# 2017_CARTE_MOFSET.net
KiCad netlist of a schematic drawn in Altium Designer
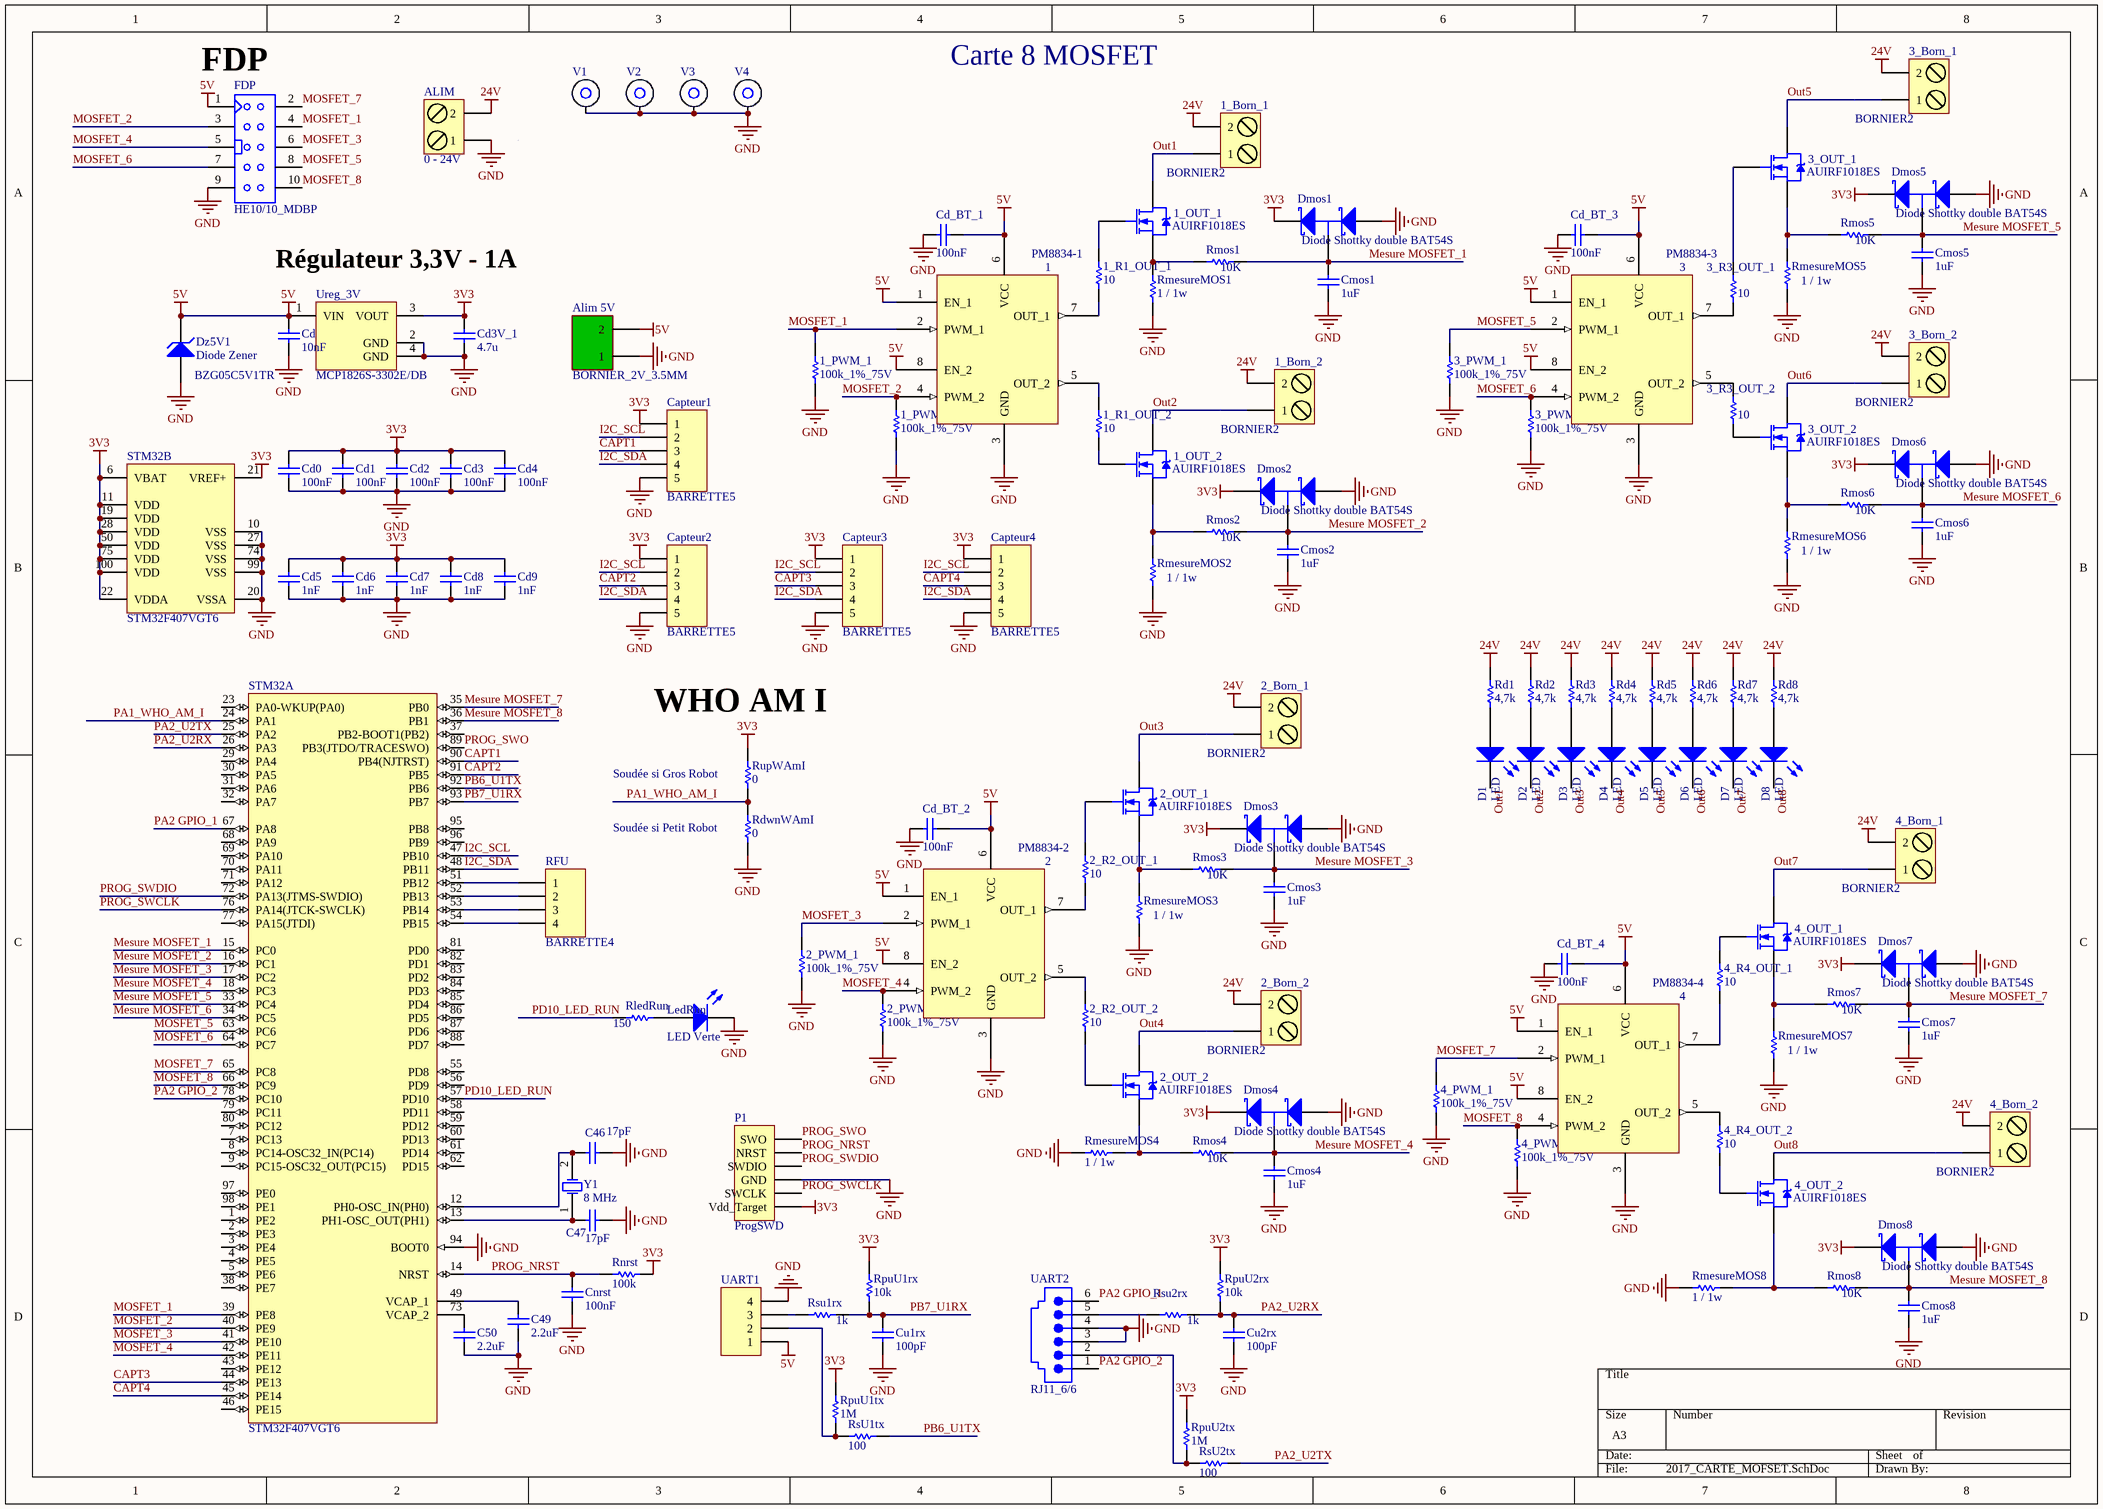
[diagram p0: 2017_CARTE_MOFSET.SchDoc]

(export (version "E")
  (design (tool "Eeschema 10.0.6"))
  (components
    (comp (ref "1")
      (value "PM8834-1")
      (footprint "SO8_N")
      (description "4 A dual low-side MOSFET driver")
      (libsource (lib "_ROBOT") (part "PM8834"))
    )
    (comp (ref "1_Born_1")
      (value "BORNIER2")
      (footprint "BORNIER2")
      (description "Terminal blocks, 2 pins, pitch=5mm")
      (libsource (lib "Connecteur") (part "BORNIER2"))
    )
    (comp (ref "1_Born_2")
      (value "BORNIER2")
      (footprint "BORNIER2")
      (description "Terminal blocks, 2 pins, pitch=5mm")
      (libsource (lib "Connecteur") (part "BORNIER2"))
    )
    (comp (ref "1_OUT_1")
      (value "AUIRF1018ES")
      (footprint "D2PAK_GROS_PAD")
      (description "HEXFET N-Channel Power MOSFET")
      (fields (field (name "PUBLISHER") "Altium Limited"))
      (libsource (lib "IR Discrete MOSFET - Power") (part "IRF1010S"))
    )
    (comp (ref "1_OUT_2")
      (value "AUIRF1018ES")
      (footprint "D2PAK_GROS_PAD")
      (description "HEXFET N-Channel Power MOSFET")
      (fields (field (name "PUBLISHER") "Altium Limited"))
      (libsource (lib "IR Discrete MOSFET - Power") (part "IRF1010S"))
    )
    (comp (ref "1_PWM_1")
      (value "100k_1%_75V")
      (footprint "R1206_N")
      (description "Resistor")
      (fields (field (name "PUBLISHER") "Altium Limited"))
      (libsource (lib "DG_Resistance") (part "Resistor"))
    )
    (comp (ref "1_PWM_2")
      (value "100k_1%_75V")
      (footprint "R1206_N")
      (description "Resistor")
      (fields (field (name "PUBLISHER") "Altium Limited"))
      (libsource (lib "DG_Resistance") (part "Resistor"))
    )
    (comp (ref "1_R1_OUT_1")
      (value "10")
      (footprint "R1206_N")
      (description "Resistor")
      (fields (field (name "PUBLISHER") "Altium Limited"))
      (libsource (lib "_ROBOT") (part "Resistor"))
    )
    (comp (ref "1_R1_OUT_2")
      (value "10")
      (footprint "R1206_N")
      (description "Resistor")
      (fields (field (name "PUBLISHER") "Altium Limited"))
      (libsource (lib "_ROBOT") (part "Resistor"))
    )
    (comp (ref "2")
      (value "PM8834-2")
      (footprint "SO8_N")
      (description "4 A dual low-side MOSFET driver")
      (libsource (lib "_ROBOT") (part "PM8834"))
    )
    (comp (ref "2_Born_1")
      (value "BORNIER2")
      (footprint "BORNIER2")
      (description "Terminal blocks, 2 pins, pitch=5mm")
      (libsource (lib "Connecteur") (part "BORNIER2"))
    )
    (comp (ref "2_Born_2")
      (value "BORNIER2")
      (footprint "BORNIER2")
      (description "Terminal blocks, 2 pins, pitch=5mm")
      (libsource (lib "Connecteur") (part "BORNIER2"))
    )
    (comp (ref "2_OUT_1")
      (value "AUIRF1018ES")
      (footprint "D2PAK_GROS_PAD")
      (description "HEXFET N-Channel Power MOSFET")
      (fields (field (name "PUBLISHER") "Altium Limited"))
      (libsource (lib "IR Discrete MOSFET - Power") (part "IRF1010S"))
    )
    (comp (ref "2_OUT_2")
      (value "AUIRF1018ES")
      (footprint "D2PAK_GROS_PAD")
      (description "HEXFET N-Channel Power MOSFET")
      (fields (field (name "PUBLISHER") "Altium Limited"))
      (libsource (lib "IR Discrete MOSFET - Power") (part "IRF1010S"))
    )
    (comp (ref "2_PWM_1")
      (value "100k_1%_75V")
      (footprint "R1206_N")
      (description "Resistor")
      (fields (field (name "PUBLISHER") "Altium Limited"))
      (libsource (lib "DG_Resistance") (part "Resistor"))
    )
    (comp (ref "2_PWM_2")
      (value "100k_1%_75V")
      (footprint "R1206_N")
      (description "Resistor")
      (fields (field (name "PUBLISHER") "Altium Limited"))
      (libsource (lib "DG_Resistance") (part "Resistor"))
    )
    (comp (ref "2_R2_OUT_1")
      (value "10")
      (footprint "R1206_N")
      (description "Resistor")
      (fields (field (name "PUBLISHER") "Altium Limited"))
      (libsource (lib "_ROBOT") (part "Resistor"))
    )
    (comp (ref "2_R2_OUT_2")
      (value "10")
      (footprint "R1206_N")
      (description "Resistor")
      (fields (field (name "PUBLISHER") "Altium Limited"))
      (libsource (lib "_ROBOT") (part "Resistor"))
    )
    (comp (ref "3")
      (value "PM8834-3")
      (footprint "SO8_N")
      (description "4 A dual low-side MOSFET driver")
      (libsource (lib "_ROBOT") (part "PM8834"))
    )
    (comp (ref "3_Born_1")
      (value "BORNIER2")
      (footprint "BORNIER2")
      (description "Terminal blocks, 2 pins, pitch=5mm")
      (libsource (lib "Connecteur") (part "BORNIER2"))
    )
    (comp (ref "3_Born_2")
      (value "BORNIER2")
      (footprint "BORNIER2")
      (description "Terminal blocks, 2 pins, pitch=5mm")
      (libsource (lib "Connecteur") (part "BORNIER2"))
    )
    (comp (ref "3_OUT_1")
      (value "AUIRF1018ES")
      (footprint "D2PAK_GROS_PAD")
      (description "HEXFET N-Channel Power MOSFET")
      (fields (field (name "PUBLISHER") "Altium Limited"))
      (libsource (lib "IR Discrete MOSFET - Power") (part "IRF1010S"))
    )
    (comp (ref "3_OUT_2")
      (value "AUIRF1018ES")
      (footprint "D2PAK_GROS_PAD")
      (description "HEXFET N-Channel Power MOSFET")
      (fields (field (name "PUBLISHER") "Altium Limited"))
      (libsource (lib "IR Discrete MOSFET - Power") (part "IRF1010S"))
    )
    (comp (ref "3_PWM_1")
      (value "100k_1%_75V")
      (footprint "R1206_N")
      (description "Resistor")
      (fields (field (name "PUBLISHER") "Altium Limited"))
      (libsource (lib "DG_Resistance") (part "Resistor"))
    )
    (comp (ref "3_PWM_2")
      (value "100k_1%_75V")
      (footprint "R1206_N")
      (description "Resistor")
      (fields (field (name "PUBLISHER") "Altium Limited"))
      (libsource (lib "DG_Resistance") (part "Resistor"))
    )
    (comp (ref "3_R3_OUT_1")
      (value "10")
      (footprint "R1206_N")
      (description "Resistor")
      (fields (field (name "PUBLISHER") "Altium Limited"))
      (libsource (lib "_ROBOT") (part "Resistor"))
    )
    (comp (ref "3_R3_OUT_2")
      (value "10")
      (footprint "R1206_N")
      (description "Resistor")
      (fields (field (name "PUBLISHER") "Altium Limited"))
      (libsource (lib "_ROBOT") (part "Resistor"))
    )
    (comp (ref "4")
      (value "PM8834-4")
      (footprint "SO8_N")
      (description "4 A dual low-side MOSFET driver")
      (libsource (lib "_ROBOT") (part "PM8834"))
    )
    (comp (ref "4_Born_1")
      (value "BORNIER2")
      (footprint "BORNIER2")
      (description "Terminal blocks, 2 pins, pitch=5mm")
      (libsource (lib "Connecteur") (part "BORNIER2"))
    )
    (comp (ref "4_Born_2")
      (value "BORNIER2")
      (footprint "BORNIER2")
      (description "Terminal blocks, 2 pins, pitch=5mm")
      (libsource (lib "Connecteur") (part "BORNIER2"))
    )
    (comp (ref "4_OUT_1")
      (value "AUIRF1018ES")
      (footprint "D2PAK_GROS_PAD")
      (description "HEXFET N-Channel Power MOSFET")
      (fields (field (name "PUBLISHER") "Altium Limited"))
      (libsource (lib "IR Discrete MOSFET - Power") (part "IRF1010S"))
    )
    (comp (ref "4_OUT_2")
      (value "AUIRF1018ES")
      (footprint "D2PAK_GROS_PAD")
      (description "HEXFET N-Channel Power MOSFET")
      (fields (field (name "PUBLISHER") "Altium Limited"))
      (libsource (lib "IR Discrete MOSFET - Power") (part "IRF1010S"))
    )
    (comp (ref "4_PWM_1")
      (value "100k_1%_75V")
      (footprint "R1206_N")
      (description "Resistor")
      (fields (field (name "PUBLISHER") "Altium Limited"))
      (libsource (lib "DG_Resistance") (part "Resistor"))
    )
    (comp (ref "4_PWM_2")
      (value "100k_1%_75V")
      (footprint "R1206_N")
      (description "Resistor")
      (fields (field (name "PUBLISHER") "Altium Limited"))
      (libsource (lib "DG_Resistance") (part "Resistor"))
    )
    (comp (ref "4_R4_OUT_1")
      (value "10")
      (footprint "R1206_N")
      (description "Resistor")
      (fields (field (name "PUBLISHER") "Altium Limited"))
      (libsource (lib "_ROBOT") (part "Resistor"))
    )
    (comp (ref "4_R4_OUT_2")
      (value "10")
      (footprint "R1206_N")
      (description "Resistor")
      (fields (field (name "PUBLISHER") "Altium Limited"))
      (libsource (lib "_ROBOT") (part "Resistor"))
    )
    (comp (ref "ALIM")
      (value "0 - 24V")
      (footprint "BORNIER2_FEM_COUDE")
      (description "Terminal blocks, 2 pins, pitch=5mm")
      (libsource (lib "miniprojet") (part "BORNIER2"))
    )
    (comp (ref "Alim 5V")
      (value "BORNIER_2V_3.5MM")
      (footprint "BORNIER_2V_3.5MM")
      (libsource (lib "Connecteur") (part "BORNIER_2V_3.5MM"))
    )
    (comp (ref "C46")
      (value "17pF")
      (footprint "C0805_N")
      (description "Capacitor")
      (fields (field (name "PUBLISHER") "Altium Limited"))
      (libsource (lib "_ROBOT") (part "Condensateur"))
    )
    (comp (ref "C47")
      (value "17pF")
      (footprint "C0805_N")
      (description "Capacitor")
      (fields (field (name "PUBLISHER") "Altium Limited"))
      (libsource (lib "_ROBOT") (part "Condensateur"))
    )
    (comp (ref "C49")
      (value "2.2uF")
      (footprint "C0805_N")
      (description "Capacitor")
      (fields (field (name "PUBLISHER") "Altium Limited"))
      (libsource (lib "_ROBOT") (part "Condensateur"))
    )
    (comp (ref "C50")
      (value "2.2uF")
      (footprint "C0805_N")
      (description "Capacitor")
      (fields (field (name "PUBLISHER") "Altium Limited"))
      (libsource (lib "_ROBOT") (part "Condensateur"))
    )
    (comp (ref "Capteur1")
      (value "BARRETTE5")
      (footprint "MOLEX5_2.50MM")
      (description "Header, 5-Pin")
      (fields (field (name "PUBLISHER") "Altium Limited"))
      (libsource (lib "Connecteur") (part "BARRETTE5"))
    )
    (comp (ref "Capteur2")
      (value "BARRETTE5")
      (footprint "MOLEX5_2.50MM")
      (description "Header, 5-Pin")
      (fields (field (name "PUBLISHER") "Altium Limited"))
      (libsource (lib "Connecteur") (part "BARRETTE5"))
    )
    (comp (ref "Capteur3")
      (value "BARRETTE5")
      (footprint "MOLEX5_2.50MM")
      (description "Header, 5-Pin")
      (fields (field (name "PUBLISHER") "Altium Limited"))
      (libsource (lib "Connecteur") (part "BARRETTE5"))
    )
    (comp (ref "Capteur4")
      (value "BARRETTE5")
      (footprint "MOLEX5_2.50MM")
      (description "Header, 5-Pin")
      (fields (field (name "PUBLISHER") "Altium Limited"))
      (libsource (lib "Connecteur") (part "BARRETTE5"))
    )
    (comp (ref "Cd")
      (value "10nF")
      (footprint "C1206_N")
      (description "Capacitor")
      (fields (field (name "PUBLISHER") "Altium Limited"))
      (libsource (lib "_ROBOT") (part "Condensateur"))
    )
    (comp (ref "Cd0")
      (value "100nF")
      (footprint "C0805_N")
      (description "Capacitor")
      (fields (field (name "PUBLISHER") "Altium Limited"))
      (libsource (lib "_ROBOT") (part "Condensateur"))
    )
    (comp (ref "Cd1")
      (value "100nF")
      (footprint "C0805_N")
      (description "Capacitor")
      (fields (field (name "PUBLISHER") "Altium Limited"))
      (libsource (lib "_ROBOT") (part "Condensateur"))
    )
    (comp (ref "Cd2")
      (value "100nF")
      (footprint "C0805_N")
      (description "Capacitor")
      (fields (field (name "PUBLISHER") "Altium Limited"))
      (libsource (lib "_ROBOT") (part "Condensateur"))
    )
    (comp (ref "Cd3")
      (value "100nF")
      (footprint "C0805_N")
      (description "Capacitor")
      (fields (field (name "PUBLISHER") "Altium Limited"))
      (libsource (lib "_ROBOT") (part "Condensateur"))
    )
    (comp (ref "Cd3V_1")
      (value "4.7u")
      (footprint "C0805_N")
      (description "Capacitor")
      (fields (field (name "PUBLISHER") "Altium Limited"))
      (libsource (lib "DG_Condensateur") (part "Capacitor"))
    )
    (comp (ref "Cd4")
      (value "100nF")
      (footprint "C0805_N")
      (description "Capacitor")
      (fields (field (name "PUBLISHER") "Altium Limited"))
      (libsource (lib "_ROBOT") (part "Condensateur"))
    )
    (comp (ref "Cd5")
      (value "1nF")
      (footprint "C0805_N")
      (description "Capacitor")
      (fields (field (name "PUBLISHER") "Altium Limited"))
      (libsource (lib "_ROBOT") (part "Condensateur"))
    )
    (comp (ref "Cd6")
      (value "1nF")
      (footprint "C0805_N")
      (description "Capacitor")
      (fields (field (name "PUBLISHER") "Altium Limited"))
      (libsource (lib "_ROBOT") (part "Condensateur"))
    )
    (comp (ref "Cd7")
      (value "1nF")
      (footprint "C0805_N")
      (description "Capacitor")
      (fields (field (name "PUBLISHER") "Altium Limited"))
      (libsource (lib "_ROBOT") (part "Condensateur"))
    )
    (comp (ref "Cd8")
      (value "1nF")
      (footprint "C0805_N")
      (description "Capacitor")
      (fields (field (name "PUBLISHER") "Altium Limited"))
      (libsource (lib "_ROBOT") (part "Condensateur"))
    )
    (comp (ref "Cd9")
      (value "1nF")
      (footprint "C0805_N")
      (description "Capacitor")
      (fields (field (name "PUBLISHER") "Altium Limited"))
      (libsource (lib "_ROBOT") (part "Condensateur"))
    )
    (comp (ref "Cd_BT_1")
      (value "100nF")
      (footprint "C0805_N")
      (description "Capacitor")
      (fields (field (name "PUBLISHER") "Altium Limited"))
      (libsource (lib "_ROBOT") (part "Condensateur"))
    )
    (comp (ref "Cd_BT_2")
      (value "100nF")
      (footprint "C0805_N")
      (description "Capacitor")
      (fields (field (name "PUBLISHER") "Altium Limited"))
      (libsource (lib "_ROBOT") (part "Condensateur"))
    )
    (comp (ref "Cd_BT_3")
      (value "100nF")
      (footprint "C0805_N")
      (description "Capacitor")
      (fields (field (name "PUBLISHER") "Altium Limited"))
      (libsource (lib "_ROBOT") (part "Condensateur"))
    )
    (comp (ref "Cd_BT_4")
      (value "100nF")
      (footprint "C0805_N")
      (description "Capacitor")
      (fields (field (name "PUBLISHER") "Altium Limited"))
      (libsource (lib "_ROBOT") (part "Condensateur"))
    )
    (comp (ref "Cmos1")
      (value "1uF")
      (footprint "C0805_N")
      (description "Capacitor")
      (fields (field (name "PUBLISHER") "Altium Limited"))
      (libsource (lib "_ROBOT") (part "Condensateur"))
    )
    (comp (ref "Cmos2")
      (value "1uF")
      (footprint "C0805_N")
      (description "Capacitor")
      (fields (field (name "PUBLISHER") "Altium Limited"))
      (libsource (lib "_ROBOT") (part "Condensateur"))
    )
    (comp (ref "Cmos3")
      (value "1uF")
      (footprint "C0805_N")
      (description "Capacitor")
      (fields (field (name "PUBLISHER") "Altium Limited"))
      (libsource (lib "_ROBOT") (part "Condensateur"))
    )
    (comp (ref "Cmos4")
      (value "1uF")
      (footprint "C0805_N")
      (description "Capacitor")
      (fields (field (name "PUBLISHER") "Altium Limited"))
      (libsource (lib "_ROBOT") (part "Condensateur"))
    )
    (comp (ref "Cmos5")
      (value "1uF")
      (footprint "C0805_N")
      (description "Capacitor")
      (fields (field (name "PUBLISHER") "Altium Limited"))
      (libsource (lib "_ROBOT") (part "Condensateur"))
    )
    (comp (ref "Cmos6")
      (value "1uF")
      (footprint "C0805_N")
      (description "Capacitor")
      (fields (field (name "PUBLISHER") "Altium Limited"))
      (libsource (lib "_ROBOT") (part "Condensateur"))
    )
    (comp (ref "Cmos7")
      (value "1uF")
      (footprint "C0805_N")
      (description "Capacitor")
      (fields (field (name "PUBLISHER") "Altium Limited"))
      (libsource (lib "_ROBOT") (part "Condensateur"))
    )
    (comp (ref "Cmos8")
      (value "1uF")
      (footprint "C0805_N")
      (description "Capacitor")
      (fields (field (name "PUBLISHER") "Altium Limited"))
      (libsource (lib "_ROBOT") (part "Condensateur"))
    )
    (comp (ref "Cnrst")
      (value "100nF")
      (footprint "C0805_N")
      (description "Capacitor")
      (fields (field (name "PUBLISHER") "Altium Limited"))
      (libsource (lib "_ROBOT") (part "Condensateur"))
    )
    (comp (ref "Cu1rx")
      (value "100pF")
      (footprint "C0805_N")
      (description "Capacitor")
      (fields (field (name "PUBLISHER") "Altium Limited"))
      (libsource (lib "_ROBOT") (part "Condensateur"))
    )
    (comp (ref "Cu2rx")
      (value "100pF")
      (footprint "C0805_N")
      (description "Capacitor")
      (fields (field (name "PUBLISHER") "Altium Limited"))
      (libsource (lib "_ROBOT") (part "Condensateur"))
    )
    (comp (ref "D1")
      (value "LED")
      (footprint "LED_0805")
      (description "Typical LED")
      (fields (field (name "PUBLISHER") "Altium Limited"))
      (libsource (lib "_ROBOT") (part "LED"))
    )
    (comp (ref "D2")
      (value "LED")
      (footprint "LED_0805")
      (description "Typical LED")
      (fields (field (name "PUBLISHER") "Altium Limited"))
      (libsource (lib "_ROBOT") (part "LED"))
    )
    (comp (ref "D3")
      (value "LED")
      (footprint "LED_0805")
      (description "Typical LED")
      (fields (field (name "PUBLISHER") "Altium Limited"))
      (libsource (lib "_ROBOT") (part "LED"))
    )
    (comp (ref "D4")
      (value "LED")
      (footprint "LED_0805")
      (description "Typical LED")
      (fields (field (name "PUBLISHER") "Altium Limited"))
      (libsource (lib "_ROBOT") (part "LED"))
    )
    (comp (ref "D5")
      (value "LED")
      (footprint "LED_0805")
      (description "Typical LED")
      (fields (field (name "PUBLISHER") "Altium Limited"))
      (libsource (lib "_ROBOT") (part "LED"))
    )
    (comp (ref "D6")
      (value "LED")
      (footprint "LED_0805")
      (description "Typical LED")
      (fields (field (name "PUBLISHER") "Altium Limited"))
      (libsource (lib "_ROBOT") (part "LED"))
    )
    (comp (ref "D7")
      (value "LED")
      (footprint "LED_0805")
      (description "Typical LED")
      (fields (field (name "PUBLISHER") "Altium Limited"))
      (libsource (lib "_ROBOT") (part "LED"))
    )
    (comp (ref "D8")
      (value "LED")
      (footprint "LED_0805")
      (description "Typical LED")
      (fields (field (name "PUBLISHER") "Altium Limited"))
      (libsource (lib "_ROBOT") (part "LED"))
    )
    (comp (ref "Dmos1")
      (value "Diode Shottky double BAT54S")
      (footprint "SOT23-3N")
      (description "DIODE SCHOTTKY DOUBLE")
      (fields (field (name "MANUFACTURER PART NUMBER") "BAT54S") (field (name "MANUFACTURER") "ZETEX"))
      (libsource (lib "_ROBOT") (part "Diode Shottky double BAT54S"))
    )
    (comp (ref "Dmos2")
      (value "Diode Shottky double BAT54S")
      (footprint "SOT23-3N")
      (description "DIODE SCHOTTKY DOUBLE")
      (fields (field (name "MANUFACTURER PART NUMBER") "BAT54S") (field (name "MANUFACTURER") "ZETEX"))
      (libsource (lib "_ROBOT") (part "Diode Shottky double BAT54S"))
    )
    (comp (ref "Dmos3")
      (value "Diode Shottky double BAT54S")
      (footprint "SOT23-3N")
      (description "DIODE SCHOTTKY DOUBLE")
      (fields (field (name "MANUFACTURER PART NUMBER") "BAT54S") (field (name "MANUFACTURER") "ZETEX"))
      (libsource (lib "_ROBOT") (part "Diode Shottky double BAT54S"))
    )
    (comp (ref "Dmos4")
      (value "Diode Shottky double BAT54S")
      (footprint "SOT23-3N")
      (description "DIODE SCHOTTKY DOUBLE")
      (fields (field (name "MANUFACTURER PART NUMBER") "BAT54S") (field (name "MANUFACTURER") "ZETEX"))
      (libsource (lib "_ROBOT") (part "Diode Shottky double BAT54S"))
    )
    (comp (ref "Dmos5")
      (value "Diode Shottky double BAT54S")
      (footprint "SOT23-3N")
      (description "DIODE SCHOTTKY DOUBLE")
      (fields (field (name "MANUFACTURER PART NUMBER") "BAT54S") (field (name "MANUFACTURER") "ZETEX"))
      (libsource (lib "_ROBOT") (part "Diode Shottky double BAT54S"))
    )
    (comp (ref "Dmos6")
      (value "Diode Shottky double BAT54S")
      (footprint "SOT23-3N")
      (description "DIODE SCHOTTKY DOUBLE")
      (fields (field (name "MANUFACTURER PART NUMBER") "BAT54S") (field (name "MANUFACTURER") "ZETEX"))
      (libsource (lib "_ROBOT") (part "Diode Shottky double BAT54S"))
    )
    (comp (ref "Dmos7")
      (value "Diode Shottky double BAT54S")
      (footprint "SOT23-3N")
      (description "DIODE SCHOTTKY DOUBLE")
      (fields (field (name "MANUFACTURER PART NUMBER") "BAT54S") (field (name "MANUFACTURER") "ZETEX"))
      (libsource (lib "_ROBOT") (part "Diode Shottky double BAT54S"))
    )
    (comp (ref "Dmos8")
      (value "Diode Shottky double BAT54S")
      (footprint "SOT23-3N")
      (description "DIODE SCHOTTKY DOUBLE")
      (fields (field (name "MANUFACTURER PART NUMBER") "BAT54S") (field (name "MANUFACTURER") "ZETEX"))
      (libsource (lib "_ROBOT") (part "Diode Shottky double BAT54S"))
    )
    (comp (ref "Dz5V1")
      (value "Diode Zener")
      (footprint "SMA Diode")
      (description "Zener Diode")
      (fields (field (name "ALTIUM_UNNAMED_1") "BZG05C5V1TR"))
      (libsource (lib "_ROBOT") (part "Diode Zener"))
    )
    (comp (ref "FDP")
      (value "HE10/10_MALE_DROIT_BAS_PROFIL")
      (footprint "HE10/10_M_D_BP")
      (description "EMBASE HE10/10 MALE DROIT BAS PROFIL")
      (fields (field (name "TYPE") "HE10/10_MDBP"))
      (libsource (lib "connecteurs") (part "HE10/10_MALE_DROIT_BAS_PROFIL"))
    )
    (comp (ref "LedRun")
      (value "LED Verte")
      (footprint "LED_0805")
      (description "Typical LED")
      (fields (field (name "PUBLISHER") "Altium Limited"))
      (libsource (lib "DG_LED") (part "LED"))
    )
    (comp (ref "P1")
      (value "ProgSWD")
      (footprint "HDR1X6")
      (description "Header, 6-Pin")
      (fields (field (name "PUBLISHER") "Altium Limited"))
      (libsource (lib "DG_Connecteur") (part "Header 6"))
    )
    (comp (ref "Rd1")
      (value "4,7k")
      (footprint "R1206_N")
      (description "Resistor")
      (fields (field (name "PUBLISHER") "Altium Limited"))
      (libsource (lib "_ROBOT") (part "Resistor"))
    )
    (comp (ref "Rd2")
      (value "4,7k")
      (footprint "R1206_N")
      (description "Resistor")
      (fields (field (name "PUBLISHER") "Altium Limited"))
      (libsource (lib "_ROBOT") (part "Resistor"))
    )
    (comp (ref "Rd3")
      (value "4,7k")
      (footprint "R1206_N")
      (description "Resistor")
      (fields (field (name "PUBLISHER") "Altium Limited"))
      (libsource (lib "_ROBOT") (part "Resistor"))
    )
    (comp (ref "Rd4")
      (value "4,7k")
      (footprint "R1206_N")
      (description "Resistor")
      (fields (field (name "PUBLISHER") "Altium Limited"))
      (libsource (lib "_ROBOT") (part "Resistor"))
    )
    (comp (ref "Rd5")
      (value "4,7k")
      (footprint "R1206_N")
      (description "Resistor")
      (fields (field (name "PUBLISHER") "Altium Limited"))
      (libsource (lib "_ROBOT") (part "Resistor"))
    )
    (comp (ref "Rd6")
      (value "4,7k")
      (footprint "R1206_N")
      (description "Resistor")
      (fields (field (name "PUBLISHER") "Altium Limited"))
      (libsource (lib "_ROBOT") (part "Resistor"))
    )
    (comp (ref "Rd7")
      (value "4,7k")
      (footprint "R1206_N")
      (description "Resistor")
      (fields (field (name "PUBLISHER") "Altium Limited"))
      (libsource (lib "_ROBOT") (part "Resistor"))
    )
    (comp (ref "Rd8")
      (value "4,7k")
      (footprint "R1206_N")
      (description "Resistor")
      (fields (field (name "PUBLISHER") "Altium Limited"))
      (libsource (lib "_ROBOT") (part "Resistor"))
    )
    (comp (ref "RdwnWAmI")
      (value "0")
      (footprint "R1206_N")
      (description "Resistor")
      (fields (field (name "PUBLISHER") "Altium Limited"))
      (libsource (lib "_ROBOT") (part "Resistor"))
    )
    (comp (ref "RFU")
      (value "BARRETTE4")
      (footprint "HE14_4")
      (description "Header, 4-Pin")
      (fields (field (name "PUBLISHER") "Altium Limited"))
      (libsource (lib "Connecteur") (part "BARRETTE4"))
    )
    (comp (ref "RledRun")
      (value "150")
      (footprint "R1206_N")
      (description "Resistor")
      (fields (field (name "PUBLISHER") "Altium Limited"))
      (libsource (lib "_ROBOT") (part "Resistor"))
    )
    (comp (ref "RmesureMOS1")
      (value "1 / 1w")
      (footprint "INDUCTANCE_CMS_1812")
      (description "Resistor")
      (fields (field (name "PUBLISHER") "Altium Limited"))
      (libsource (lib "_ROBOT") (part "Resistor"))
    )
    (comp (ref "RmesureMOS2")
      (value "1 / 1w")
      (footprint "INDUCTANCE_CMS_1812")
      (description "Resistor")
      (fields (field (name "PUBLISHER") "Altium Limited"))
      (libsource (lib "_ROBOT") (part "Resistor"))
    )
    (comp (ref "RmesureMOS3")
      (value "1 / 1w")
      (footprint "INDUCTANCE_CMS_1812")
      (description "Resistor")
      (fields (field (name "PUBLISHER") "Altium Limited"))
      (libsource (lib "_ROBOT") (part "Resistor"))
    )
    (comp (ref "RmesureMOS4")
      (value "1 / 1w")
      (footprint "INDUCTANCE_CMS_1812")
      (description "Resistor")
      (fields (field (name "PUBLISHER") "Altium Limited"))
      (libsource (lib "_ROBOT") (part "Resistor"))
    )
    (comp (ref "RmesureMOS5")
      (value "1 / 1w")
      (footprint "INDUCTANCE_CMS_1812")
      (description "Resistor")
      (fields (field (name "PUBLISHER") "Altium Limited"))
      (libsource (lib "_ROBOT") (part "Resistor"))
    )
    (comp (ref "RmesureMOS6")
      (value "1 / 1w")
      (footprint "INDUCTANCE_CMS_1812")
      (description "Resistor")
      (fields (field (name "PUBLISHER") "Altium Limited"))
      (libsource (lib "_ROBOT") (part "Resistor"))
    )
    (comp (ref "RmesureMOS7")
      (value "1 / 1w")
      (footprint "INDUCTANCE_CMS_1812")
      (description "Resistor")
      (fields (field (name "PUBLISHER") "Altium Limited"))
      (libsource (lib "_ROBOT") (part "Resistor"))
    )
    (comp (ref "RmesureMOS8")
      (value "1 / 1w")
      (footprint "INDUCTANCE_CMS_1812")
      (description "Resistor")
      (fields (field (name "PUBLISHER") "Altium Limited"))
      (libsource (lib "_ROBOT") (part "Resistor"))
    )
    (comp (ref "Rmos1")
      (value "10K")
      (footprint "R1206_N")
      (description "Resistor")
      (fields (field (name "PUBLISHER") "Altium Limited"))
      (libsource (lib "_ROBOT") (part "Resistor"))
    )
    (comp (ref "Rmos2")
      (value "10K")
      (footprint "R1206_N")
      (description "Resistor")
      (fields (field (name "PUBLISHER") "Altium Limited"))
      (libsource (lib "_ROBOT") (part "Resistor"))
    )
    (comp (ref "Rmos3")
      (value "10K")
      (footprint "R1206_N")
      (description "Resistor")
      (fields (field (name "PUBLISHER") "Altium Limited"))
      (libsource (lib "_ROBOT") (part "Resistor"))
    )
    (comp (ref "Rmos4")
      (value "10K")
      (footprint "R1206_N")
      (description "Resistor")
      (fields (field (name "PUBLISHER") "Altium Limited"))
      (libsource (lib "_ROBOT") (part "Resistor"))
    )
    (comp (ref "Rmos5")
      (value "10K")
      (footprint "R1206_N")
      (description "Resistor")
      (fields (field (name "PUBLISHER") "Altium Limited"))
      (libsource (lib "_ROBOT") (part "Resistor"))
    )
    (comp (ref "Rmos6")
      (value "10K")
      (footprint "R1206_N")
      (description "Resistor")
      (fields (field (name "PUBLISHER") "Altium Limited"))
      (libsource (lib "_ROBOT") (part "Resistor"))
    )
    (comp (ref "Rmos7")
      (value "10K")
      (footprint "R1206_N")
      (description "Resistor")
      (fields (field (name "PUBLISHER") "Altium Limited"))
      (libsource (lib "_ROBOT") (part "Resistor"))
    )
    (comp (ref "Rmos8")
      (value "10K")
      (footprint "R1206_N")
      (description "Resistor")
      (fields (field (name "PUBLISHER") "Altium Limited"))
      (libsource (lib "_ROBOT") (part "Resistor"))
    )
    (comp (ref "Rnrst")
      (value "100k")
      (footprint "R1206_N")
      (description "Resistor")
      (fields (field (name "PUBLISHER") "Altium Limited"))
      (libsource (lib "_ROBOT") (part "Resistor"))
    )
    (comp (ref "RpuU1rx")
      (value "10k")
      (footprint "R1206_N")
      (description "Resistor")
      (fields (field (name "PUBLISHER") "Altium Limited"))
      (libsource (lib "_ROBOT") (part "Resistor"))
    )
    (comp (ref "RpuU1tx")
      (value "1M")
      (footprint "R1206_N")
      (description "Resistor")
      (fields (field (name "PUBLISHER") "Altium Limited"))
      (libsource (lib "_ROBOT") (part "Resistor"))
    )
    (comp (ref "RpuU2rx")
      (value "10k")
      (footprint "R1206_N")
      (description "Resistor")
      (fields (field (name "PUBLISHER") "Altium Limited"))
      (libsource (lib "_ROBOT") (part "Resistor"))
    )
    (comp (ref "RpuU2tx")
      (value "1M")
      (footprint "R1206_N")
      (description "Resistor")
      (fields (field (name "PUBLISHER") "Altium Limited"))
      (libsource (lib "_ROBOT") (part "Resistor"))
    )
    (comp (ref "Rsu1rx")
      (value "1k")
      (footprint "R1206_N")
      (description "Resistor")
      (fields (field (name "PUBLISHER") "Altium Limited"))
      (libsource (lib "_ROBOT") (part "Resistor"))
    )
    (comp (ref "RsU1tx")
      (value "100")
      (footprint "R1206_N")
      (description "Resistor")
      (fields (field (name "PUBLISHER") "Altium Limited"))
      (libsource (lib "_ROBOT") (part "Resistor"))
    )
    (comp (ref "Rsu2rx")
      (value "1k")
      (footprint "R1206_N")
      (description "Resistor")
      (fields (field (name "PUBLISHER") "Altium Limited"))
      (libsource (lib "_ROBOT") (part "Resistor"))
    )
    (comp (ref "RsU2tx")
      (value "100")
      (footprint "R1206_N")
      (description "Resistor")
      (fields (field (name "PUBLISHER") "Altium Limited"))
      (libsource (lib "_ROBOT") (part "Resistor"))
    )
    (comp (ref "RupWAmI")
      (value "0")
      (footprint "R1206_N")
      (description "Resistor")
      (fields (field (name "PUBLISHER") "Altium Limited"))
      (libsource (lib "_ROBOT") (part "Resistor"))
    )
    (comp (ref "STM32")
      (value "STM32F407VGT6")
      (footprint "STM-LQFP100_N")
      (fields (field (name "MANUFACTURER") "STMicroelectronics"))
      (libsource (lib "STMicroelectronics STM32 F4") (part "STM32F407VGT6"))
    )
    (comp (ref "UART1")
      (value "BARRETTE4")
      (footprint "HDR1X4")
      (description "Header, 4-Pin")
      (fields (field (name "PUBLISHER") "Altium Limited"))
      (libsource (lib "Connecteur") (part "HDR1X4"))
    )
    (comp (ref "UART2")
      (value "RJ11_6/6")
      (footprint "RJ11_6/6")
      (description "Right Angle, Standard Profile, Offset Latch DECconnect, Flangeless PCB Jack")
      (fields (field (name "PUBLISHER") "Altium Limited"))
      (libsource (lib "Connecteur") (part "RJ11_6/6"))
    )
    (comp (ref "Ureg_3V")
      (value "MCP1826S-3302E/DB")
      (footprint "SOT223-4N")
      (description "1000 mA, Low Voltage, Low Quiescent Current LDO Regulator, 3-Pin SOT-223, Extended Temperature")
      (fields (field (name "PUBLISHER") "Altium Limited"))
      (libsource (lib "Microchip Power Mgt Line Regulator") (part "MCP1826S-3302E/DB"))
    )
    (comp (ref "V1")
      (value "Entretoise WURTH CMS")
      (footprint "ENTRETOISE_CMS")
      (description "Entretoise Wurth")
      (fields (field (name "PUBLISHER") "Damien Guitton"))
      (libsource (lib "_ROBOT") (part "Entretoise WURTH CMS"))
    )
    (comp (ref "V2")
      (value "Entretoise WURTH CMS")
      (footprint "ENTRETOISE_CMS")
      (description "Entretoise Wurth")
      (fields (field (name "PUBLISHER") "Damien Guitton"))
      (libsource (lib "_ROBOT") (part "Entretoise WURTH CMS"))
    )
    (comp (ref "V3")
      (value "Entretoise WURTH CMS")
      (footprint "ENTRETOISE_CMS")
      (description "Entretoise Wurth")
      (fields (field (name "PUBLISHER") "Damien Guitton"))
      (libsource (lib "_ROBOT") (part "Entretoise WURTH CMS"))
    )
    (comp (ref "V4")
      (value "Entretoise WURTH CMS")
      (footprint "ENTRETOISE_CMS")
      (description "Entretoise Wurth")
      (fields (field (name "PUBLISHER") "Damien Guitton"))
      (libsource (lib "_ROBOT") (part "Entretoise WURTH CMS"))
    )
    (comp (ref "Y1")
      (value "8 MHz")
      (footprint "HC49/4H_SMX")
      (description "Crystal Oscillator")
      (fields (field (name "PUBLISHER") "Altium Limited"))
      (libsource (lib "_ROBOT") (part "Quartz"))
    )
  )
  (nets
    (net (code "1") (name "/CAPT1") (class "Default")
      (node (ref "Capteur1") (pin "3") (pinfunction "3_3") (pintype "passive"))
      (node (ref "STM32") (pin "90") (pinfunction "PB4(NJTRST)_90") (pintype "bidirectional"))
    )
    (net (code "2") (name "/CAPT2") (class "Default")
      (node (ref "Capteur2") (pin "3") (pinfunction "3_3") (pintype "passive"))
      (node (ref "STM32") (pin "91") (pinfunction "PB5_91") (pintype "bidirectional"))
    )
    (net (code "3") (name "/CAPT3") (class "Default")
      (node (ref "Capteur3") (pin "3") (pinfunction "3_3") (pintype "passive"))
      (node (ref "STM32") (pin "44") (pinfunction "PE13_44") (pintype "bidirectional"))
    )
    (net (code "4") (name "/CAPT4") (class "Default")
      (node (ref "Capteur4") (pin "3") (pinfunction "3_3") (pintype "passive"))
      (node (ref "STM32") (pin "45") (pinfunction "PE14_45") (pintype "bidirectional"))
    )
    (net (code "5") (name "/I2C_SCL") (class "Default")
      (node (ref "Capteur1") (pin "2") (pinfunction "2_2") (pintype "passive"))
      (node (ref "Capteur2") (pin "2") (pinfunction "2_2") (pintype "passive"))
      (node (ref "Capteur3") (pin "2") (pinfunction "2_2") (pintype "passive"))
      (node (ref "Capteur4") (pin "2") (pinfunction "2_2") (pintype "passive"))
      (node (ref "STM32") (pin "47") (pinfunction "PB10_47") (pintype "bidirectional"))
    )
    (net (code "6") (name "/I2C_SDA") (class "Default")
      (node (ref "Capteur1") (pin "4") (pinfunction "4_4") (pintype "passive"))
      (node (ref "Capteur2") (pin "4") (pinfunction "4_4") (pintype "passive"))
      (node (ref "Capteur3") (pin "4") (pinfunction "4_4") (pintype "passive"))
      (node (ref "Capteur4") (pin "4") (pinfunction "4_4") (pintype "passive"))
      (node (ref "STM32") (pin "48") (pinfunction "PB11_48") (pintype "bidirectional"))
    )
    (net (code "7") (name "/MOSFET_1") (class "Default")
      (node (ref "1") (pin "2") (pinfunction "PWM_1_2") (pintype "input"))
      (node (ref "1_PWM_1") (pin "2") (pinfunction "2_2") (pintype "passive"))
      (node (ref "FDP") (pin "4") (pinfunction "4_4") (pintype "passive"))
      (node (ref "STM32") (pin "39") (pinfunction "PE8_39") (pintype "bidirectional"))
    )
    (net (code "8") (name "/MOSFET_2") (class "Default")
      (node (ref "1") (pin "4") (pinfunction "PWM_2_4") (pintype "input"))
      (node (ref "1_PWM_2") (pin "2") (pinfunction "2_2") (pintype "passive"))
      (node (ref "FDP") (pin "3") (pinfunction "3_3") (pintype "passive"))
      (node (ref "STM32") (pin "40") (pinfunction "PE9_40") (pintype "bidirectional"))
    )
    (net (code "9") (name "/MOSFET_3") (class "Default")
      (node (ref "2") (pin "2") (pinfunction "PWM_1_2") (pintype "input"))
      (node (ref "2_PWM_1") (pin "2") (pinfunction "2_2") (pintype "passive"))
      (node (ref "FDP") (pin "6") (pinfunction "6_6") (pintype "passive"))
      (node (ref "STM32") (pin "41") (pinfunction "PE10_41") (pintype "bidirectional"))
    )
    (net (code "10") (name "/MOSFET_4") (class "Default")
      (node (ref "2") (pin "4") (pinfunction "PWM_2_4") (pintype "input"))
      (node (ref "2_PWM_2") (pin "2") (pinfunction "2_2") (pintype "passive"))
      (node (ref "FDP") (pin "5") (pinfunction "5_5") (pintype "passive"))
      (node (ref "STM32") (pin "42") (pinfunction "PE11_42") (pintype "bidirectional"))
    )
    (net (code "11") (name "/MOSFET_5") (class "Default")
      (node (ref "3") (pin "2") (pinfunction "PWM_1_2") (pintype "input"))
      (node (ref "3_PWM_1") (pin "2") (pinfunction "2_2") (pintype "passive"))
      (node (ref "FDP") (pin "8") (pinfunction "8_8") (pintype "passive"))
      (node (ref "STM32") (pin "63") (pinfunction "PC6_63") (pintype "bidirectional"))
    )
    (net (code "12") (name "/MOSFET_6") (class "Default")
      (node (ref "3") (pin "4") (pinfunction "PWM_2_4") (pintype "input"))
      (node (ref "3_PWM_2") (pin "2") (pinfunction "2_2") (pintype "passive"))
      (node (ref "FDP") (pin "7") (pinfunction "7_7") (pintype "passive"))
      (node (ref "STM32") (pin "64") (pinfunction "PC7_64") (pintype "bidirectional"))
    )
    (net (code "13") (name "/MOSFET_7") (class "Default")
      (node (ref "4") (pin "2") (pinfunction "PWM_1_2") (pintype "input"))
      (node (ref "4_PWM_1") (pin "2") (pinfunction "2_2") (pintype "passive"))
      (node (ref "FDP") (pin "2") (pinfunction "2_2") (pintype "passive"))
      (node (ref "STM32") (pin "65") (pinfunction "PC8_65") (pintype "bidirectional"))
    )
    (net (code "14") (name "/MOSFET_8") (class "Default")
      (node (ref "4") (pin "4") (pinfunction "PWM_2_4") (pintype "input"))
      (node (ref "4_PWM_2") (pin "2") (pinfunction "2_2") (pintype "passive"))
      (node (ref "FDP") (pin "10") (pinfunction "10_10") (pintype "passive"))
      (node (ref "STM32") (pin "66") (pinfunction "PC9_66") (pintype "bidirectional"))
    )
    (net (code "15") (name "/Mesure MOSFET_1") (class "Default")
      (node (ref "Cmos1") (pin "2") (pinfunction "2_2") (pintype "passive"))
      (node (ref "Dmos1") (pin "3") (pinfunction "C_3") (pintype "passive"))
      (node (ref "Rmos1") (pin "2") (pinfunction "2_2") (pintype "passive"))
      (node (ref "STM32") (pin "15") (pinfunction "PC0_15") (pintype "bidirectional"))
    )
    (net (code "16") (name "/Mesure MOSFET_2") (class "Default")
      (node (ref "Cmos2") (pin "2") (pinfunction "2_2") (pintype "passive"))
      (node (ref "Dmos2") (pin "3") (pinfunction "C_3") (pintype "passive"))
      (node (ref "Rmos2") (pin "2") (pinfunction "2_2") (pintype "passive"))
      (node (ref "STM32") (pin "16") (pinfunction "PC1_16") (pintype "bidirectional"))
    )
    (net (code "17") (name "/Mesure MOSFET_3") (class "Default")
      (node (ref "Cmos3") (pin "2") (pinfunction "2_2") (pintype "passive"))
      (node (ref "Dmos3") (pin "3") (pinfunction "C_3") (pintype "passive"))
      (node (ref "Rmos3") (pin "2") (pinfunction "2_2") (pintype "passive"))
      (node (ref "STM32") (pin "17") (pinfunction "PC2_17") (pintype "bidirectional"))
    )
    (net (code "18") (name "/Mesure MOSFET_4") (class "Default")
      (node (ref "Cmos4") (pin "2") (pinfunction "2_2") (pintype "passive"))
      (node (ref "Dmos4") (pin "3") (pinfunction "C_3") (pintype "passive"))
      (node (ref "Rmos4") (pin "2") (pinfunction "2_2") (pintype "passive"))
      (node (ref "STM32") (pin "18") (pinfunction "PC3_18") (pintype "bidirectional"))
    )
    (net (code "19") (name "/Mesure MOSFET_5") (class "Default")
      (node (ref "Cmos5") (pin "2") (pinfunction "2_2") (pintype "passive"))
      (node (ref "Dmos5") (pin "3") (pinfunction "C_3") (pintype "passive"))
      (node (ref "Rmos5") (pin "2") (pinfunction "2_2") (pintype "passive"))
      (node (ref "STM32") (pin "33") (pinfunction "PC4_33") (pintype "bidirectional"))
    )
    (net (code "20") (name "/Mesure MOSFET_6") (class "Default")
      (node (ref "Cmos6") (pin "2") (pinfunction "2_2") (pintype "passive"))
      (node (ref "Dmos6") (pin "3") (pinfunction "C_3") (pintype "passive"))
      (node (ref "Rmos6") (pin "2") (pinfunction "2_2") (pintype "passive"))
      (node (ref "STM32") (pin "34") (pinfunction "PC5_34") (pintype "bidirectional"))
    )
    (net (code "21") (name "/Mesure MOSFET_7") (class "Default")
      (node (ref "Cmos7") (pin "2") (pinfunction "2_2") (pintype "passive"))
      (node (ref "Dmos7") (pin "3") (pinfunction "C_3") (pintype "passive"))
      (node (ref "Rmos7") (pin "2") (pinfunction "2_2") (pintype "passive"))
      (node (ref "STM32") (pin "35") (pinfunction "PB0_35") (pintype "bidirectional"))
    )
    (net (code "22") (name "/Mesure MOSFET_8") (class "Default")
      (node (ref "Cmos8") (pin "2") (pinfunction "2_2") (pintype "passive"))
      (node (ref "Dmos8") (pin "3") (pinfunction "C_3") (pintype "passive"))
      (node (ref "Rmos8") (pin "2") (pinfunction "2_2") (pintype "passive"))
      (node (ref "STM32") (pin "36") (pinfunction "PB1_36") (pintype "bidirectional"))
    )
    (net (code "23") (name "/Out1") (class "Default")
      (node (ref "1_Born_1") (pin "1") (pinfunction "1_1") (pintype "passive"))
      (node (ref "1_OUT_1") (pin "2") (pinfunction "D_2") (pintype "passive"))
      (node (ref "D1") (pin "2") (pinfunction "K_2") (pintype "passive"))
    )
    (net (code "24") (name "/Out2") (class "Default")
      (node (ref "1_Born_2") (pin "1") (pinfunction "1_1") (pintype "passive"))
      (node (ref "1_OUT_2") (pin "2") (pinfunction "D_2") (pintype "passive"))
      (node (ref "D2") (pin "2") (pinfunction "K_2") (pintype "passive"))
    )
    (net (code "25") (name "/Out3") (class "Default")
      (node (ref "2_Born_1") (pin "1") (pinfunction "1_1") (pintype "passive"))
      (node (ref "2_OUT_1") (pin "2") (pinfunction "D_2") (pintype "passive"))
      (node (ref "D3") (pin "2") (pinfunction "K_2") (pintype "passive"))
    )
    (net (code "26") (name "/Out4") (class "Default")
      (node (ref "2_Born_2") (pin "1") (pinfunction "1_1") (pintype "passive"))
      (node (ref "2_OUT_2") (pin "2") (pinfunction "D_2") (pintype "passive"))
      (node (ref "D4") (pin "2") (pinfunction "K_2") (pintype "passive"))
    )
    (net (code "27") (name "/Out5") (class "Default")
      (node (ref "3_Born_1") (pin "1") (pinfunction "1_1") (pintype "passive"))
      (node (ref "3_OUT_1") (pin "2") (pinfunction "D_2") (pintype "passive"))
      (node (ref "D5") (pin "2") (pinfunction "K_2") (pintype "passive"))
    )
    (net (code "28") (name "/Out6") (class "Default")
      (node (ref "3_Born_2") (pin "1") (pinfunction "1_1") (pintype "passive"))
      (node (ref "3_OUT_2") (pin "2") (pinfunction "D_2") (pintype "passive"))
      (node (ref "D6") (pin "2") (pinfunction "K_2") (pintype "passive"))
    )
    (net (code "29") (name "/Out7") (class "Default")
      (node (ref "4_Born_1") (pin "1") (pinfunction "1_1") (pintype "passive"))
      (node (ref "4_OUT_1") (pin "2") (pinfunction "D_2") (pintype "passive"))
      (node (ref "D7") (pin "2") (pinfunction "K_2") (pintype "passive"))
    )
    (net (code "30") (name "/Out8") (class "Default")
      (node (ref "4_Born_2") (pin "1") (pinfunction "1_1") (pintype "passive"))
      (node (ref "4_OUT_2") (pin "2") (pinfunction "D_2") (pintype "passive"))
      (node (ref "D8") (pin "2") (pinfunction "K_2") (pintype "passive"))
    )
    (net (code "31") (name "/PA1_WHO_AM_I") (class "Default")
      (node (ref "RdwnWAmI") (pin "2") (pinfunction "2_2") (pintype "passive"))
      (node (ref "RupWAmI") (pin "1") (pinfunction "1_1") (pintype "passive"))
      (node (ref "STM32") (pin "24") (pinfunction "PA1_24") (pintype "bidirectional"))
    )
    (net (code "32") (name "/PA2 GPIO_1") (class "Default")
      (node (ref "STM32") (pin "67") (pinfunction "PA8_67") (pintype "bidirectional"))
      (node (ref "UART2") (pin "6") (pinfunction "6_6") (pintype "passive"))
    )
    (net (code "33") (name "/PA2 GPIO_2") (class "Default")
      (node (ref "STM32") (pin "78") (pinfunction "PC10_78") (pintype "bidirectional"))
      (node (ref "UART2") (pin "1") (pinfunction "1_1") (pintype "passive"))
    )
    (net (code "34") (name "/PA2_U2RX") (class "Default")
      (node (ref "Cu2rx") (pin "2") (pinfunction "2_2") (pintype "passive"))
      (node (ref "RpuU2rx") (pin "1") (pinfunction "1_1") (pintype "passive"))
      (node (ref "Rsu2rx") (pin "1") (pinfunction "1_1") (pintype "passive"))
      (node (ref "STM32") (pin "26") (pinfunction "PA3_26") (pintype "bidirectional"))
    )
    (net (code "35") (name "/PA2_U2TX") (class "Default")
      (node (ref "RsU2tx") (pin "2") (pinfunction "2_2") (pintype "passive"))
      (node (ref "STM32") (pin "25") (pinfunction "PA2_25") (pintype "bidirectional"))
    )
    (net (code "36") (name "/PB6_U1TX") (class "Default")
      (node (ref "RsU1tx") (pin "2") (pinfunction "2_2") (pintype "passive"))
      (node (ref "STM32") (pin "92") (pinfunction "PB6_92") (pintype "bidirectional"))
    )
    (net (code "37") (name "/PB7_U1RX") (class "Default")
      (node (ref "Cu1rx") (pin "2") (pinfunction "2_2") (pintype "passive"))
      (node (ref "RpuU1rx") (pin "1") (pinfunction "1_1") (pintype "passive"))
      (node (ref "Rsu1rx") (pin "1") (pinfunction "1_1") (pintype "passive"))
      (node (ref "STM32") (pin "93") (pinfunction "PB7_93") (pintype "bidirectional"))
    )
    (net (code "38") (name "/PD10_LED_RUN") (class "Default")
      (node (ref "RledRun") (pin "2") (pinfunction "2_2") (pintype "passive"))
      (node (ref "STM32") (pin "57") (pinfunction "PD10_57") (pintype "bidirectional"))
    )
    (net (code "39") (name "/PROG_NRST") (class "Default")
      (node (ref "Cnrst") (pin "2") (pinfunction "2_2") (pintype "passive"))
      (node (ref "P1") (pin "5") (pinfunction "NRST_5") (pintype "passive"))
      (node (ref "Rnrst") (pin "1") (pinfunction "1_1") (pintype "passive"))
      (node (ref "STM32") (pin "14") (pinfunction "NRST_14") (pintype "bidirectional"))
    )
    (net (code "40") (name "/PROG_SWCLK") (class "Default")
      (node (ref "P1") (pin "2") (pinfunction "SWCLK_2") (pintype "passive"))
      (node (ref "STM32") (pin "76") (pinfunction "PA14(JTCK-SWCLK)_76") (pintype "bidirectional"))
    )
    (net (code "41") (name "/PROG_SWDIO") (class "Default")
      (node (ref "P1") (pin "4") (pinfunction "SWDIO_4") (pintype "passive"))
      (node (ref "STM32") (pin "72") (pinfunction "PA13(JTMS-SWDIO)_72") (pintype "bidirectional"))
    )
    (net (code "42") (name "/PROG_SWO") (class "Default")
      (node (ref "P1") (pin "6") (pinfunction "SWO_6") (pintype "passive"))
      (node (ref "STM32") (pin "89") (pinfunction "PB3(JTDO/TRACESWO)_89") (pintype "bidirectional"))
    )
    (net (code "43") (name "3V3") (class "Default")
      (node (ref "Capteur1") (pin "1") (pinfunction "1_1") (pintype "passive"))
      (node (ref "Capteur2") (pin "1") (pinfunction "1_1") (pintype "passive"))
      (node (ref "Capteur3") (pin "1") (pinfunction "1_1") (pintype "passive"))
      (node (ref "Capteur4") (pin "1") (pinfunction "1_1") (pintype "passive"))
      (node (ref "Cd0") (pin "2") (pinfunction "2_2") (pintype "passive"))
      (node (ref "Cd1") (pin "2") (pinfunction "2_2") (pintype "passive"))
      (node (ref "Cd2") (pin "2") (pinfunction "2_2") (pintype "passive"))
      (node (ref "Cd3") (pin "2") (pinfunction "2_2") (pintype "passive"))
      (node (ref "Cd3V_1") (pin "2") (pinfunction "2_2") (pintype "passive"))
      (node (ref "Cd4") (pin "2") (pinfunction "2_2") (pintype "passive"))
      (node (ref "Cd5") (pin "2") (pinfunction "2_2") (pintype "passive"))
      (node (ref "Cd6") (pin "2") (pinfunction "2_2") (pintype "passive"))
      (node (ref "Cd7") (pin "2") (pinfunction "2_2") (pintype "passive"))
      (node (ref "Cd8") (pin "2") (pinfunction "2_2") (pintype "passive"))
      (node (ref "Cd9") (pin "2") (pinfunction "2_2") (pintype "passive"))
      (node (ref "Dmos1") (pin "2") (pinfunction "K_2") (pintype "passive"))
      (node (ref "Dmos2") (pin "2") (pinfunction "K_2") (pintype "passive"))
      (node (ref "Dmos3") (pin "2") (pinfunction "K_2") (pintype "passive"))
      (node (ref "Dmos4") (pin "2") (pinfunction "K_2") (pintype "passive"))
      (node (ref "Dmos5") (pin "2") (pinfunction "K_2") (pintype "passive"))
      (node (ref "Dmos6") (pin "2") (pinfunction "K_2") (pintype "passive"))
      (node (ref "Dmos7") (pin "2") (pinfunction "K_2") (pintype "passive"))
      (node (ref "Dmos8") (pin "2") (pinfunction "K_2") (pintype "passive"))
      (node (ref "P1") (pin "1") (pinfunction "Vdd_Target_1") (pintype "passive"))
      (node (ref "Rnrst") (pin "2") (pinfunction "2_2") (pintype "passive"))
      (node (ref "RpuU1rx") (pin "2") (pinfunction "2_2") (pintype "passive"))
      (node (ref "RpuU1tx") (pin "2") (pinfunction "2_2") (pintype "passive"))
      (node (ref "RpuU2rx") (pin "2") (pinfunction "2_2") (pintype "passive"))
      (node (ref "RpuU2tx") (pin "2") (pinfunction "2_2") (pintype "passive"))
      (node (ref "RupWAmI") (pin "2") (pinfunction "2_2") (pintype "passive"))
      (node (ref "STM32") (pin "100") (pinfunction "VDD_100") (pintype "power_in"))
      (node (ref "STM32") (pin "11") (pinfunction "VDD_11") (pintype "power_in"))
      (node (ref "STM32") (pin "19") (pinfunction "VDD_19") (pintype "power_in"))
      (node (ref "STM32") (pin "21") (pinfunction "VREF+_21") (pintype "power_in"))
      (node (ref "STM32") (pin "22") (pinfunction "VDDA_22") (pintype "power_in"))
      (node (ref "STM32") (pin "28") (pinfunction "VDD_28") (pintype "power_in"))
      (node (ref "STM32") (pin "50") (pinfunction "VDD_50") (pintype "power_in"))
      (node (ref "STM32") (pin "6") (pinfunction "VBAT_6") (pintype "power_in"))
      (node (ref "STM32") (pin "75") (pinfunction "VDD_75") (pintype "power_in"))
      (node (ref "Ureg_3V") (pin "3") (pinfunction "VOUT_3") (pintype "power_in"))
    )
    (net (code "44") (name "5V") (class "Default")
      (node (ref "1") (pin "1") (pinfunction "EN_1_1") (pintype "passive"))
      (node (ref "1") (pin "6") (pinfunction "VCC_6") (pintype "power_in"))
      (node (ref "1") (pin "8") (pinfunction "EN_2_8") (pintype "passive"))
      (node (ref "2") (pin "1") (pinfunction "EN_1_1") (pintype "passive"))
      (node (ref "2") (pin "6") (pinfunction "VCC_6") (pintype "power_in"))
      (node (ref "2") (pin "8") (pinfunction "EN_2_8") (pintype "passive"))
      (node (ref "3") (pin "1") (pinfunction "EN_1_1") (pintype "passive"))
      (node (ref "3") (pin "6") (pinfunction "VCC_6") (pintype "power_in"))
      (node (ref "3") (pin "8") (pinfunction "EN_2_8") (pintype "passive"))
      (node (ref "4") (pin "1") (pinfunction "EN_1_1") (pintype "passive"))
      (node (ref "4") (pin "6") (pinfunction "VCC_6") (pintype "power_in"))
      (node (ref "4") (pin "8") (pinfunction "EN_2_8") (pintype "passive"))
      (node (ref "Alim 5V") (pin "2") (pinfunction "2_2") (pintype "passive"))
      (node (ref "Cd") (pin "2") (pinfunction "2_2") (pintype "passive"))
      (node (ref "Cd_BT_1") (pin "2") (pinfunction "2_2") (pintype "passive"))
      (node (ref "Cd_BT_2") (pin "2") (pinfunction "2_2") (pintype "passive"))
      (node (ref "Cd_BT_3") (pin "2") (pinfunction "2_2") (pintype "passive"))
      (node (ref "Cd_BT_4") (pin "2") (pinfunction "2_2") (pintype "passive"))
      (node (ref "Dz5V1") (pin "2") (pinfunction "K_2") (pintype "passive"))
      (node (ref "FDP") (pin "1") (pinfunction "1_1") (pintype "passive"))
      (node (ref "UART1") (pin "1") (pinfunction "1_1") (pintype "passive"))
      (node (ref "Ureg_3V") (pin "1") (pinfunction "VIN_1") (pintype "power_in"))
    )
    (net (code "45") (name "24V") (class "Default")
      (node (ref "1_Born_1") (pin "2") (pinfunction "2_2") (pintype "passive"))
      (node (ref "1_Born_2") (pin "2") (pinfunction "2_2") (pintype "passive"))
      (node (ref "2_Born_1") (pin "2") (pinfunction "2_2") (pintype "passive"))
      (node (ref "2_Born_2") (pin "2") (pinfunction "2_2") (pintype "passive"))
      (node (ref "3_Born_1") (pin "2") (pinfunction "2_2") (pintype "passive"))
      (node (ref "3_Born_2") (pin "2") (pinfunction "2_2") (pintype "passive"))
      (node (ref "4_Born_1") (pin "2") (pinfunction "2_2") (pintype "passive"))
      (node (ref "4_Born_2") (pin "2") (pinfunction "2_2") (pintype "passive"))
      (node (ref "ALIM") (pin "2") (pinfunction "2_2") (pintype "passive"))
      (node (ref "Rd1") (pin "1") (pinfunction "1_1") (pintype "passive"))
      (node (ref "Rd2") (pin "1") (pinfunction "1_1") (pintype "passive"))
      (node (ref "Rd3") (pin "1") (pinfunction "1_1") (pintype "passive"))
      (node (ref "Rd4") (pin "1") (pinfunction "1_1") (pintype "passive"))
      (node (ref "Rd5") (pin "1") (pinfunction "1_1") (pintype "passive"))
      (node (ref "Rd6") (pin "1") (pinfunction "1_1") (pintype "passive"))
      (node (ref "Rd7") (pin "1") (pinfunction "1_1") (pintype "passive"))
      (node (ref "Rd8") (pin "1") (pinfunction "1_1") (pintype "passive"))
    )
    (net (code "46") (name "GND") (class "Default")
      (node (ref "1") (pin "3") (pinfunction "GND_3") (pintype "power_in"))
      (node (ref "1_PWM_1") (pin "1") (pinfunction "1_1") (pintype "passive"))
      (node (ref "1_PWM_2") (pin "1") (pinfunction "1_1") (pintype "passive"))
      (node (ref "2") (pin "3") (pinfunction "GND_3") (pintype "power_in"))
      (node (ref "2_PWM_1") (pin "1") (pinfunction "1_1") (pintype "passive"))
      (node (ref "2_PWM_2") (pin "1") (pinfunction "1_1") (pintype "passive"))
      (node (ref "3") (pin "3") (pinfunction "GND_3") (pintype "power_in"))
      (node (ref "3_PWM_1") (pin "1") (pinfunction "1_1") (pintype "passive"))
      (node (ref "3_PWM_2") (pin "1") (pinfunction "1_1") (pintype "passive"))
      (node (ref "4") (pin "3") (pinfunction "GND_3") (pintype "power_in"))
      (node (ref "4_PWM_1") (pin "1") (pinfunction "1_1") (pintype "passive"))
      (node (ref "4_PWM_2") (pin "1") (pinfunction "1_1") (pintype "passive"))
      (node (ref "ALIM") (pin "1") (pinfunction "1_1") (pintype "passive"))
      (node (ref "Alim 5V") (pin "1") (pinfunction "1_1") (pintype "passive"))
      (node (ref "C46") (pin "1") (pinfunction "1_1") (pintype "passive"))
      (node (ref "C47") (pin "1") (pinfunction "1_1") (pintype "passive"))
      (node (ref "C49") (pin "1") (pinfunction "1_1") (pintype "passive"))
      (node (ref "C50") (pin "1") (pinfunction "1_1") (pintype "passive"))
      (node (ref "Capteur1") (pin "5") (pinfunction "5_5") (pintype "passive"))
      (node (ref "Capteur2") (pin "5") (pinfunction "5_5") (pintype "passive"))
      (node (ref "Capteur3") (pin "5") (pinfunction "5_5") (pintype "passive"))
      (node (ref "Capteur4") (pin "5") (pinfunction "5_5") (pintype "passive"))
      (node (ref "Cd") (pin "1") (pinfunction "1_1") (pintype "passive"))
      (node (ref "Cd0") (pin "1") (pinfunction "1_1") (pintype "passive"))
      (node (ref "Cd1") (pin "1") (pinfunction "1_1") (pintype "passive"))
      (node (ref "Cd2") (pin "1") (pinfunction "1_1") (pintype "passive"))
      (node (ref "Cd3") (pin "1") (pinfunction "1_1") (pintype "passive"))
      (node (ref "Cd3V_1") (pin "1") (pinfunction "1_1") (pintype "passive"))
      (node (ref "Cd4") (pin "1") (pinfunction "1_1") (pintype "passive"))
      (node (ref "Cd5") (pin "1") (pinfunction "1_1") (pintype "passive"))
      (node (ref "Cd6") (pin "1") (pinfunction "1_1") (pintype "passive"))
      (node (ref "Cd7") (pin "1") (pinfunction "1_1") (pintype "passive"))
      (node (ref "Cd8") (pin "1") (pinfunction "1_1") (pintype "passive"))
      (node (ref "Cd9") (pin "1") (pinfunction "1_1") (pintype "passive"))
      (node (ref "Cd_BT_1") (pin "1") (pinfunction "1_1") (pintype "passive"))
      (node (ref "Cd_BT_2") (pin "1") (pinfunction "1_1") (pintype "passive"))
      (node (ref "Cd_BT_3") (pin "1") (pinfunction "1_1") (pintype "passive"))
      (node (ref "Cd_BT_4") (pin "1") (pinfunction "1_1") (pintype "passive"))
      (node (ref "Cmos1") (pin "1") (pinfunction "1_1") (pintype "passive"))
      (node (ref "Cmos2") (pin "1") (pinfunction "1_1") (pintype "passive"))
      (node (ref "Cmos3") (pin "1") (pinfunction "1_1") (pintype "passive"))
      (node (ref "Cmos4") (pin "1") (pinfunction "1_1") (pintype "passive"))
      (node (ref "Cmos5") (pin "1") (pinfunction "1_1") (pintype "passive"))
      (node (ref "Cmos6") (pin "1") (pinfunction "1_1") (pintype "passive"))
      (node (ref "Cmos7") (pin "1") (pinfunction "1_1") (pintype "passive"))
      (node (ref "Cmos8") (pin "1") (pinfunction "1_1") (pintype "passive"))
      (node (ref "Cnrst") (pin "1") (pinfunction "1_1") (pintype "passive"))
      (node (ref "Cu1rx") (pin "1") (pinfunction "1_1") (pintype "passive"))
      (node (ref "Cu2rx") (pin "1") (pinfunction "1_1") (pintype "passive"))
      (node (ref "Dmos1") (pin "1") (pinfunction "A_1") (pintype "passive"))
      (node (ref "Dmos2") (pin "1") (pinfunction "A_1") (pintype "passive"))
      (node (ref "Dmos3") (pin "1") (pinfunction "A_1") (pintype "passive"))
      (node (ref "Dmos4") (pin "1") (pinfunction "A_1") (pintype "passive"))
      (node (ref "Dmos5") (pin "1") (pinfunction "A_1") (pintype "passive"))
      (node (ref "Dmos6") (pin "1") (pinfunction "A_1") (pintype "passive"))
      (node (ref "Dmos7") (pin "1") (pinfunction "A_1") (pintype "passive"))
      (node (ref "Dmos8") (pin "1") (pinfunction "A_1") (pintype "passive"))
      (node (ref "Dz5V1") (pin "1") (pinfunction "A_1") (pintype "passive"))
      (node (ref "FDP") (pin "9") (pinfunction "9_9") (pintype "passive"))
      (node (ref "LedRun") (pin "2") (pinfunction "K_2") (pintype "passive"))
      (node (ref "P1") (pin "3") (pinfunction "GND_3") (pintype "passive"))
      (node (ref "RdwnWAmI") (pin "1") (pinfunction "1_1") (pintype "passive"))
      (node (ref "RmesureMOS1") (pin "1") (pinfunction "1_1") (pintype "passive"))
      (node (ref "RmesureMOS2") (pin "1") (pinfunction "1_1") (pintype "passive"))
      (node (ref "RmesureMOS3") (pin "1") (pinfunction "1_1") (pintype "passive"))
      (node (ref "RmesureMOS4") (pin "2") (pinfunction "2_2") (pintype "passive"))
      (node (ref "RmesureMOS5") (pin "1") (pinfunction "1_1") (pintype "passive"))
      (node (ref "RmesureMOS6") (pin "1") (pinfunction "1_1") (pintype "passive"))
      (node (ref "RmesureMOS7") (pin "1") (pinfunction "1_1") (pintype "passive"))
      (node (ref "RmesureMOS8") (pin "2") (pinfunction "2_2") (pintype "passive"))
      (node (ref "STM32") (pin "10") (pinfunction "VSS_10") (pintype "power_in"))
      (node (ref "STM32") (pin "20") (pinfunction "VSSA_20") (pintype "power_in"))
      (node (ref "STM32") (pin "27") (pinfunction "VSS_27") (pintype "power_in"))
      (node (ref "STM32") (pin "74") (pinfunction "VSS_74") (pintype "power_in"))
      (node (ref "STM32") (pin "94") (pinfunction "BOOT0_94") (pintype "input"))
      (node (ref "STM32") (pin "99") (pinfunction "VSS_99") (pintype "power_in"))
      (node (ref "UART1") (pin "4") (pinfunction "4_4") (pintype "passive"))
      (node (ref "UART2") (pin "3") (pinfunction "3_3") (pintype "passive"))
      (node (ref "UART2") (pin "4") (pinfunction "4_4") (pintype "passive"))
      (node (ref "Ureg_3V") (pin "2") (pinfunction "GND_2") (pintype "power_in"))
      (node (ref "Ureg_3V") (pin "4") (pinfunction "GND_4") (pintype "power_in"))
      (node (ref "V1") (pin "1") (pinfunction "1_1") (pintype "passive"))
      (node (ref "V2") (pin "1") (pinfunction "1_1") (pintype "passive"))
      (node (ref "V3") (pin "1") (pinfunction "1_1") (pintype "passive"))
      (node (ref "V4") (pin "1") (pinfunction "1_1") (pintype "passive"))
    )
    (net (code "47") (name "Net-(1-OUT_1)") (class "Default")
      (node (ref "1") (pin "7") (pinfunction "OUT_1_7") (pintype "output"))
      (node (ref "1_R1_OUT_1") (pin "1") (pinfunction "1_1") (pintype "passive"))
    )
    (net (code "48") (name "Net-(1-OUT_2)") (class "Default")
      (node (ref "1") (pin "5") (pinfunction "OUT_2_5") (pintype "output"))
      (node (ref "1_R1_OUT_2") (pin "2") (pinfunction "2_2") (pintype "passive"))
    )
    (net (code "49") (name "Net-(1_OUT_1-G)") (class "Default")
      (node (ref "1_OUT_1") (pin "1") (pinfunction "G_1") (pintype "passive"))
      (node (ref "1_R1_OUT_1") (pin "2") (pinfunction "2_2") (pintype "passive"))
    )
    (net (code "50") (name "Net-(1_OUT_1-S)") (class "Default")
      (node (ref "1_OUT_1") (pin "3") (pinfunction "S_3") (pintype "passive"))
      (node (ref "RmesureMOS1") (pin "2") (pinfunction "2_2") (pintype "passive"))
      (node (ref "Rmos1") (pin "1") (pinfunction "1_1") (pintype "passive"))
    )
    (net (code "51") (name "Net-(1_OUT_2-G)") (class "Default")
      (node (ref "1_OUT_2") (pin "1") (pinfunction "G_1") (pintype "passive"))
      (node (ref "1_R1_OUT_2") (pin "1") (pinfunction "1_1") (pintype "passive"))
    )
    (net (code "52") (name "Net-(1_OUT_2-S)") (class "Default")
      (node (ref "1_OUT_2") (pin "3") (pinfunction "S_3") (pintype "passive"))
      (node (ref "RmesureMOS2") (pin "2") (pinfunction "2_2") (pintype "passive"))
      (node (ref "Rmos2") (pin "1") (pinfunction "1_1") (pintype "passive"))
    )
    (net (code "53") (name "Net-(2-OUT_1)") (class "Default")
      (node (ref "2") (pin "7") (pinfunction "OUT_1_7") (pintype "output"))
      (node (ref "2_R2_OUT_1") (pin "1") (pinfunction "1_1") (pintype "passive"))
    )
    (net (code "54") (name "Net-(2-OUT_2)") (class "Default")
      (node (ref "2") (pin "5") (pinfunction "OUT_2_5") (pintype "output"))
      (node (ref "2_R2_OUT_2") (pin "2") (pinfunction "2_2") (pintype "passive"))
    )
    (net (code "55") (name "Net-(2_OUT_1-G)") (class "Default")
      (node (ref "2_OUT_1") (pin "1") (pinfunction "G_1") (pintype "passive"))
      (node (ref "2_R2_OUT_1") (pin "2") (pinfunction "2_2") (pintype "passive"))
    )
    (net (code "56") (name "Net-(2_OUT_1-S)") (class "Default")
      (node (ref "2_OUT_1") (pin "3") (pinfunction "S_3") (pintype "passive"))
      (node (ref "RmesureMOS3") (pin "2") (pinfunction "2_2") (pintype "passive"))
      (node (ref "Rmos3") (pin "1") (pinfunction "1_1") (pintype "passive"))
    )
    (net (code "57") (name "Net-(2_OUT_2-G)") (class "Default")
      (node (ref "2_OUT_2") (pin "1") (pinfunction "G_1") (pintype "passive"))
      (node (ref "2_R2_OUT_2") (pin "1") (pinfunction "1_1") (pintype "passive"))
    )
    (net (code "58") (name "Net-(2_OUT_2-S)") (class "Default")
      (node (ref "2_OUT_2") (pin "3") (pinfunction "S_3") (pintype "passive"))
      (node (ref "RmesureMOS4") (pin "1") (pinfunction "1_1") (pintype "passive"))
      (node (ref "Rmos4") (pin "1") (pinfunction "1_1") (pintype "passive"))
    )
    (net (code "59") (name "Net-(3-OUT_1)") (class "Default")
      (node (ref "3") (pin "7") (pinfunction "OUT_1_7") (pintype "output"))
      (node (ref "3_R3_OUT_1") (pin "1") (pinfunction "1_1") (pintype "passive"))
    )
    (net (code "60") (name "Net-(3-OUT_2)") (class "Default")
      (node (ref "3") (pin "5") (pinfunction "OUT_2_5") (pintype "output"))
      (node (ref "3_R3_OUT_2") (pin "2") (pinfunction "2_2") (pintype "passive"))
    )
    (net (code "61") (name "Net-(3_OUT_1-G)") (class "Default")
      (node (ref "3_OUT_1") (pin "1") (pinfunction "G_1") (pintype "passive"))
      (node (ref "3_R3_OUT_1") (pin "2") (pinfunction "2_2") (pintype "passive"))
    )
    (net (code "62") (name "Net-(3_OUT_1-S)") (class "Default")
      (node (ref "3_OUT_1") (pin "3") (pinfunction "S_3") (pintype "passive"))
      (node (ref "RmesureMOS5") (pin "2") (pinfunction "2_2") (pintype "passive"))
      (node (ref "Rmos5") (pin "1") (pinfunction "1_1") (pintype "passive"))
    )
    (net (code "63") (name "Net-(3_OUT_2-G)") (class "Default")
      (node (ref "3_OUT_2") (pin "1") (pinfunction "G_1") (pintype "passive"))
      (node (ref "3_R3_OUT_2") (pin "1") (pinfunction "1_1") (pintype "passive"))
    )
    (net (code "64") (name "Net-(3_OUT_2-S)") (class "Default")
      (node (ref "3_OUT_2") (pin "3") (pinfunction "S_3") (pintype "passive"))
      (node (ref "RmesureMOS6") (pin "2") (pinfunction "2_2") (pintype "passive"))
      (node (ref "Rmos6") (pin "1") (pinfunction "1_1") (pintype "passive"))
    )
    (net (code "65") (name "Net-(4-OUT_1)") (class "Default")
      (node (ref "4") (pin "7") (pinfunction "OUT_1_7") (pintype "output"))
      (node (ref "4_R4_OUT_1") (pin "1") (pinfunction "1_1") (pintype "passive"))
    )
    (net (code "66") (name "Net-(4-OUT_2)") (class "Default")
      (node (ref "4") (pin "5") (pinfunction "OUT_2_5") (pintype "output"))
      (node (ref "4_R4_OUT_2") (pin "2") (pinfunction "2_2") (pintype "passive"))
    )
    (net (code "67") (name "Net-(4_OUT_1-G)") (class "Default")
      (node (ref "4_OUT_1") (pin "1") (pinfunction "G_1") (pintype "passive"))
      (node (ref "4_R4_OUT_1") (pin "2") (pinfunction "2_2") (pintype "passive"))
    )
    (net (code "68") (name "Net-(4_OUT_1-S)") (class "Default")
      (node (ref "4_OUT_1") (pin "3") (pinfunction "S_3") (pintype "passive"))
      (node (ref "RmesureMOS7") (pin "2") (pinfunction "2_2") (pintype "passive"))
      (node (ref "Rmos7") (pin "1") (pinfunction "1_1") (pintype "passive"))
    )
    (net (code "69") (name "Net-(4_OUT_2-G)") (class "Default")
      (node (ref "4_OUT_2") (pin "1") (pinfunction "G_1") (pintype "passive"))
      (node (ref "4_R4_OUT_2") (pin "1") (pinfunction "1_1") (pintype "passive"))
    )
    (net (code "70") (name "Net-(4_OUT_2-S)") (class "Default")
      (node (ref "4_OUT_2") (pin "3") (pinfunction "S_3") (pintype "passive"))
      (node (ref "RmesureMOS8") (pin "1") (pinfunction "1_1") (pintype "passive"))
      (node (ref "Rmos8") (pin "1") (pinfunction "1_1") (pintype "passive"))
    )
    (net (code "71") (name "Net-(D1-A)") (class "Default")
      (node (ref "D1") (pin "1") (pinfunction "A_1") (pintype "passive"))
      (node (ref "Rd1") (pin "2") (pinfunction "2_2") (pintype "passive"))
    )
    (net (code "72") (name "Net-(D2-A)") (class "Default")
      (node (ref "D2") (pin "1") (pinfunction "A_1") (pintype "passive"))
      (node (ref "Rd2") (pin "2") (pinfunction "2_2") (pintype "passive"))
    )
    (net (code "73") (name "Net-(D3-A)") (class "Default")
      (node (ref "D3") (pin "1") (pinfunction "A_1") (pintype "passive"))
      (node (ref "Rd3") (pin "2") (pinfunction "2_2") (pintype "passive"))
    )
    (net (code "74") (name "Net-(D4-A)") (class "Default")
      (node (ref "D4") (pin "1") (pinfunction "A_1") (pintype "passive"))
      (node (ref "Rd4") (pin "2") (pinfunction "2_2") (pintype "passive"))
    )
    (net (code "75") (name "Net-(D5-A)") (class "Default")
      (node (ref "D5") (pin "1") (pinfunction "A_1") (pintype "passive"))
      (node (ref "Rd5") (pin "2") (pinfunction "2_2") (pintype "passive"))
    )
    (net (code "76") (name "Net-(D6-A)") (class "Default")
      (node (ref "D6") (pin "1") (pinfunction "A_1") (pintype "passive"))
      (node (ref "Rd6") (pin "2") (pinfunction "2_2") (pintype "passive"))
    )
    (net (code "77") (name "Net-(D7-A)") (class "Default")
      (node (ref "D7") (pin "1") (pinfunction "A_1") (pintype "passive"))
      (node (ref "Rd7") (pin "2") (pinfunction "2_2") (pintype "passive"))
    )
    (net (code "78") (name "Net-(D8-A)") (class "Default")
      (node (ref "D8") (pin "1") (pinfunction "A_1") (pintype "passive"))
      (node (ref "Rd8") (pin "2") (pinfunction "2_2") (pintype "passive"))
    )
    (net (code "79") (name "Net-(LedRun-A)") (class "Default")
      (node (ref "LedRun") (pin "1") (pinfunction "A_1") (pintype "passive"))
      (node (ref "RledRun") (pin "1") (pinfunction "1_1") (pintype "passive"))
    )
    (net (code "80") (name "Net-(RpuU1tx-Pad1)") (class "Default")
      (node (ref "RpuU1tx") (pin "1") (pinfunction "1_1") (pintype "passive"))
      (node (ref "RsU1tx") (pin "1") (pinfunction "1_1") (pintype "passive"))
      (node (ref "UART1") (pin "2") (pinfunction "2_2") (pintype "passive"))
    )
    (net (code "81") (name "Net-(RpuU2tx-Pad1)") (class "Default")
      (node (ref "RpuU2tx") (pin "1") (pinfunction "1_1") (pintype "passive"))
      (node (ref "RsU2tx") (pin "1") (pinfunction "1_1") (pintype "passive"))
      (node (ref "UART2") (pin "2") (pinfunction "2_2") (pintype "passive"))
    )
    (net (code "82") (name "Net-(Rsu1rx-Pad2)") (class "Default")
      (node (ref "Rsu1rx") (pin "2") (pinfunction "2_2") (pintype "passive"))
      (node (ref "UART1") (pin "3") (pinfunction "3_3") (pintype "passive"))
    )
    (net (code "83") (name "Net-(Rsu2rx-Pad2)") (class "Default")
      (node (ref "Rsu2rx") (pin "2") (pinfunction "2_2") (pintype "passive"))
      (node (ref "UART2") (pin "5") (pinfunction "5_5") (pintype "passive"))
    )
    (net (code "84") (name "Net-(STM32A-PB12)") (class "Default")
      (node (ref "RFU") (pin "1") (pinfunction "1_1") (pintype "passive"))
      (node (ref "STM32") (pin "51") (pinfunction "PB12_51") (pintype "bidirectional"))
    )
    (net (code "85") (name "Net-(STM32A-PB13)") (class "Default")
      (node (ref "RFU") (pin "2") (pinfunction "2_2") (pintype "passive"))
      (node (ref "STM32") (pin "52") (pinfunction "PB13_52") (pintype "bidirectional"))
    )
    (net (code "86") (name "Net-(STM32A-PB14)") (class "Default")
      (node (ref "RFU") (pin "3") (pinfunction "3_3") (pintype "passive"))
      (node (ref "STM32") (pin "53") (pinfunction "PB14_53") (pintype "bidirectional"))
    )
    (net (code "87") (name "Net-(STM32A-PB15)") (class "Default")
      (node (ref "RFU") (pin "4") (pinfunction "4_4") (pintype "passive"))
      (node (ref "STM32") (pin "54") (pinfunction "PB15_54") (pintype "bidirectional"))
    )
    (net (code "88") (name "Net-(STM32A-PH0-OSC_IN(PH0))") (class "Default")
      (node (ref "C46") (pin "2") (pinfunction "2_2") (pintype "passive"))
      (node (ref "STM32") (pin "12") (pinfunction "PH0-OSC_IN(PH0)_12") (pintype "bidirectional"))
      (node (ref "Y1") (pin "2") (pinfunction "OSC2_2") (pintype "passive"))
    )
    (net (code "89") (name "Net-(STM32A-PH1-OSC_OUT(PH1))") (class "Default")
      (node (ref "C47") (pin "2") (pinfunction "2_2") (pintype "passive"))
      (node (ref "STM32") (pin "13") (pinfunction "PH1-OSC_OUT(PH1)_13") (pintype "bidirectional"))
      (node (ref "Y1") (pin "1") (pinfunction "OSC1_1") (pintype "passive"))
    )
    (net (code "90") (name "Net-(STM32A-VCAP_1)") (class "Default")
      (node (ref "C49") (pin "2") (pinfunction "2_2") (pintype "passive"))
      (node (ref "STM32") (pin "49") (pinfunction "VCAP_1_49") (pintype "power_in"))
    )
    (net (code "91") (name "Net-(STM32A-VCAP_2)") (class "Default")
      (node (ref "C50") (pin "2") (pinfunction "2_2") (pintype "passive"))
      (node (ref "STM32") (pin "73") (pinfunction "VCAP_2_73") (pintype "power_in"))
    )
    (net (code "92") (name "unconnected-(STM32A-PA0-WKUP(PA0)-Pad23)") (class "Default")
      (node (ref "STM32") (pin "23") (pinfunction "PA0-WKUP(PA0)_23") (pintype "bidirectional"))
    )
    (net (code "93") (name "unconnected-(STM32A-PA4-Pad29)") (class "Default")
      (node (ref "STM32") (pin "29") (pinfunction "PA4_29") (pintype "bidirectional"))
    )
    (net (code "94") (name "unconnected-(STM32A-PA5-Pad30)") (class "Default")
      (node (ref "STM32") (pin "30") (pinfunction "PA5_30") (pintype "bidirectional"))
    )
    (net (code "95") (name "unconnected-(STM32A-PA6-Pad31)") (class "Default")
      (node (ref "STM32") (pin "31") (pinfunction "PA6_31") (pintype "bidirectional"))
    )
    (net (code "96") (name "unconnected-(STM32A-PA7-Pad32)") (class "Default")
      (node (ref "STM32") (pin "32") (pinfunction "PA7_32") (pintype "bidirectional"))
    )
    (net (code "97") (name "unconnected-(STM32A-PA9-Pad68)") (class "Default")
      (node (ref "STM32") (pin "68") (pinfunction "PA9_68") (pintype "bidirectional"))
    )
    (net (code "98") (name "unconnected-(STM32A-PA10-Pad69)") (class "Default")
      (node (ref "STM32") (pin "69") (pinfunction "PA10_69") (pintype "bidirectional"))
    )
    (net (code "99") (name "unconnected-(STM32A-PA11-Pad70)") (class "Default")
      (node (ref "STM32") (pin "70") (pinfunction "PA11_70") (pintype "bidirectional"))
    )
    (net (code "100") (name "unconnected-(STM32A-PA12-Pad71)") (class "Default")
      (node (ref "STM32") (pin "71") (pinfunction "PA12_71") (pintype "bidirectional"))
    )
    (net (code "101") (name "unconnected-(STM32A-PA15(JTDI)-Pad77)") (class "Default")
      (node (ref "STM32") (pin "77") (pinfunction "PA15(JTDI)_77") (pintype "bidirectional"))
    )
    (net (code "102") (name "unconnected-(STM32A-PB2-BOOT1(PB2)-Pad37)") (class "Default")
      (node (ref "STM32") (pin "37") (pinfunction "PB2-BOOT1(PB2)_37") (pintype "bidirectional"))
    )
    (net (code "103") (name "unconnected-(STM32A-PB8-Pad95)") (class "Default")
      (node (ref "STM32") (pin "95") (pinfunction "PB8_95") (pintype "bidirectional"))
    )
    (net (code "104") (name "unconnected-(STM32A-PB9-Pad96)") (class "Default")
      (node (ref "STM32") (pin "96") (pinfunction "PB9_96") (pintype "bidirectional"))
    )
    (net (code "105") (name "unconnected-(STM32A-PC11-Pad79)") (class "Default")
      (node (ref "STM32") (pin "79") (pinfunction "PC11_79") (pintype "bidirectional"))
    )
    (net (code "106") (name "unconnected-(STM32A-PC12-Pad80)") (class "Default")
      (node (ref "STM32") (pin "80") (pinfunction "PC12_80") (pintype "bidirectional"))
    )
    (net (code "107") (name "unconnected-(STM32A-PC13-Pad7)") (class "Default")
      (node (ref "STM32") (pin "7") (pinfunction "PC13_7") (pintype "bidirectional"))
    )
    (net (code "108") (name "unconnected-(STM32A-PC14-OSC32_IN(PC14)-Pad8)") (class "Default")
      (node (ref "STM32") (pin "8") (pinfunction "PC14-OSC32_IN(PC14)_8") (pintype "bidirectional"))
    )
    (net (code "109") (name "unconnected-(STM32A-PC15-OSC32_OUT(PC15)-Pad9)") (class "Default")
      (node (ref "STM32") (pin "9") (pinfunction "PC15-OSC32_OUT(PC15)_9") (pintype "bidirectional"))
    )
    (net (code "110") (name "unconnected-(STM32A-PD0-Pad81)") (class "Default")
      (node (ref "STM32") (pin "81") (pinfunction "PD0_81") (pintype "bidirectional"))
    )
    (net (code "111") (name "unconnected-(STM32A-PD1-Pad82)") (class "Default")
      (node (ref "STM32") (pin "82") (pinfunction "PD1_82") (pintype "bidirectional"))
    )
    (net (code "112") (name "unconnected-(STM32A-PD2-Pad83)") (class "Default")
      (node (ref "STM32") (pin "83") (pinfunction "PD2_83") (pintype "bidirectional"))
    )
    (net (code "113") (name "unconnected-(STM32A-PD3-Pad84)") (class "Default")
      (node (ref "STM32") (pin "84") (pinfunction "PD3_84") (pintype "bidirectional"))
    )
    (net (code "114") (name "unconnected-(STM32A-PD4-Pad85)") (class "Default")
      (node (ref "STM32") (pin "85") (pinfunction "PD4_85") (pintype "bidirectional"))
    )
    (net (code "115") (name "unconnected-(STM32A-PD5-Pad86)") (class "Default")
      (node (ref "STM32") (pin "86") (pinfunction "PD5_86") (pintype "bidirectional"))
    )
    (net (code "116") (name "unconnected-(STM32A-PD6-Pad87)") (class "Default")
      (node (ref "STM32") (pin "87") (pinfunction "PD6_87") (pintype "bidirectional"))
    )
    (net (code "117") (name "unconnected-(STM32A-PD7-Pad88)") (class "Default")
      (node (ref "STM32") (pin "88") (pinfunction "PD7_88") (pintype "bidirectional"))
    )
    (net (code "118") (name "unconnected-(STM32A-PD8-Pad55)") (class "Default")
      (node (ref "STM32") (pin "55") (pinfunction "PD8_55") (pintype "bidirectional"))
    )
    (net (code "119") (name "unconnected-(STM32A-PD9-Pad56)") (class "Default")
      (node (ref "STM32") (pin "56") (pinfunction "PD9_56") (pintype "bidirectional"))
    )
    (net (code "120") (name "unconnected-(STM32A-PD11-Pad58)") (class "Default")
      (node (ref "STM32") (pin "58") (pinfunction "PD11_58") (pintype "bidirectional"))
    )
    (net (code "121") (name "unconnected-(STM32A-PD12-Pad59)") (class "Default")
      (node (ref "STM32") (pin "59") (pinfunction "PD12_59") (pintype "bidirectional"))
    )
    (net (code "122") (name "unconnected-(STM32A-PD13-Pad60)") (class "Default")
      (node (ref "STM32") (pin "60") (pinfunction "PD13_60") (pintype "bidirectional"))
    )
    (net (code "123") (name "unconnected-(STM32A-PD14-Pad61)") (class "Default")
      (node (ref "STM32") (pin "61") (pinfunction "PD14_61") (pintype "bidirectional"))
    )
    (net (code "124") (name "unconnected-(STM32A-PD15-Pad62)") (class "Default")
      (node (ref "STM32") (pin "62") (pinfunction "PD15_62") (pintype "bidirectional"))
    )
    (net (code "125") (name "unconnected-(STM32A-PE0-Pad97)") (class "Default")
      (node (ref "STM32") (pin "97") (pinfunction "PE0_97") (pintype "bidirectional"))
    )
    (net (code "126") (name "unconnected-(STM32A-PE1-Pad98)") (class "Default")
      (node (ref "STM32") (pin "98") (pinfunction "PE1_98") (pintype "bidirectional"))
    )
    (net (code "127") (name "unconnected-(STM32A-PE2-Pad1)") (class "Default")
      (node (ref "STM32") (pin "1") (pinfunction "PE2_1") (pintype "bidirectional"))
    )
    (net (code "128") (name "unconnected-(STM32A-PE3-Pad2)") (class "Default")
      (node (ref "STM32") (pin "2") (pinfunction "PE3_2") (pintype "bidirectional"))
    )
    (net (code "129") (name "unconnected-(STM32A-PE4-Pad3)") (class "Default")
      (node (ref "STM32") (pin "3") (pinfunction "PE4_3") (pintype "bidirectional"))
    )
    (net (code "130") (name "unconnected-(STM32A-PE5-Pad4)") (class "Default")
      (node (ref "STM32") (pin "4") (pinfunction "PE5_4") (pintype "bidirectional"))
    )
    (net (code "131") (name "unconnected-(STM32A-PE6-Pad5)") (class "Default")
      (node (ref "STM32") (pin "5") (pinfunction "PE6_5") (pintype "bidirectional"))
    )
    (net (code "132") (name "unconnected-(STM32A-PE7-Pad38)") (class "Default")
      (node (ref "STM32") (pin "38") (pinfunction "PE7_38") (pintype "bidirectional"))
    )
    (net (code "133") (name "unconnected-(STM32A-PE12-Pad43)") (class "Default")
      (node (ref "STM32") (pin "43") (pinfunction "PE12_43") (pintype "bidirectional"))
    )
    (net (code "134") (name "unconnected-(STM32A-PE15-Pad46)") (class "Default")
      (node (ref "STM32") (pin "46") (pinfunction "PE15_46") (pintype "bidirectional"))
    )
  )
)
